# falownik_project.net
KiCad netlist of a schematic drawn in EAGLE
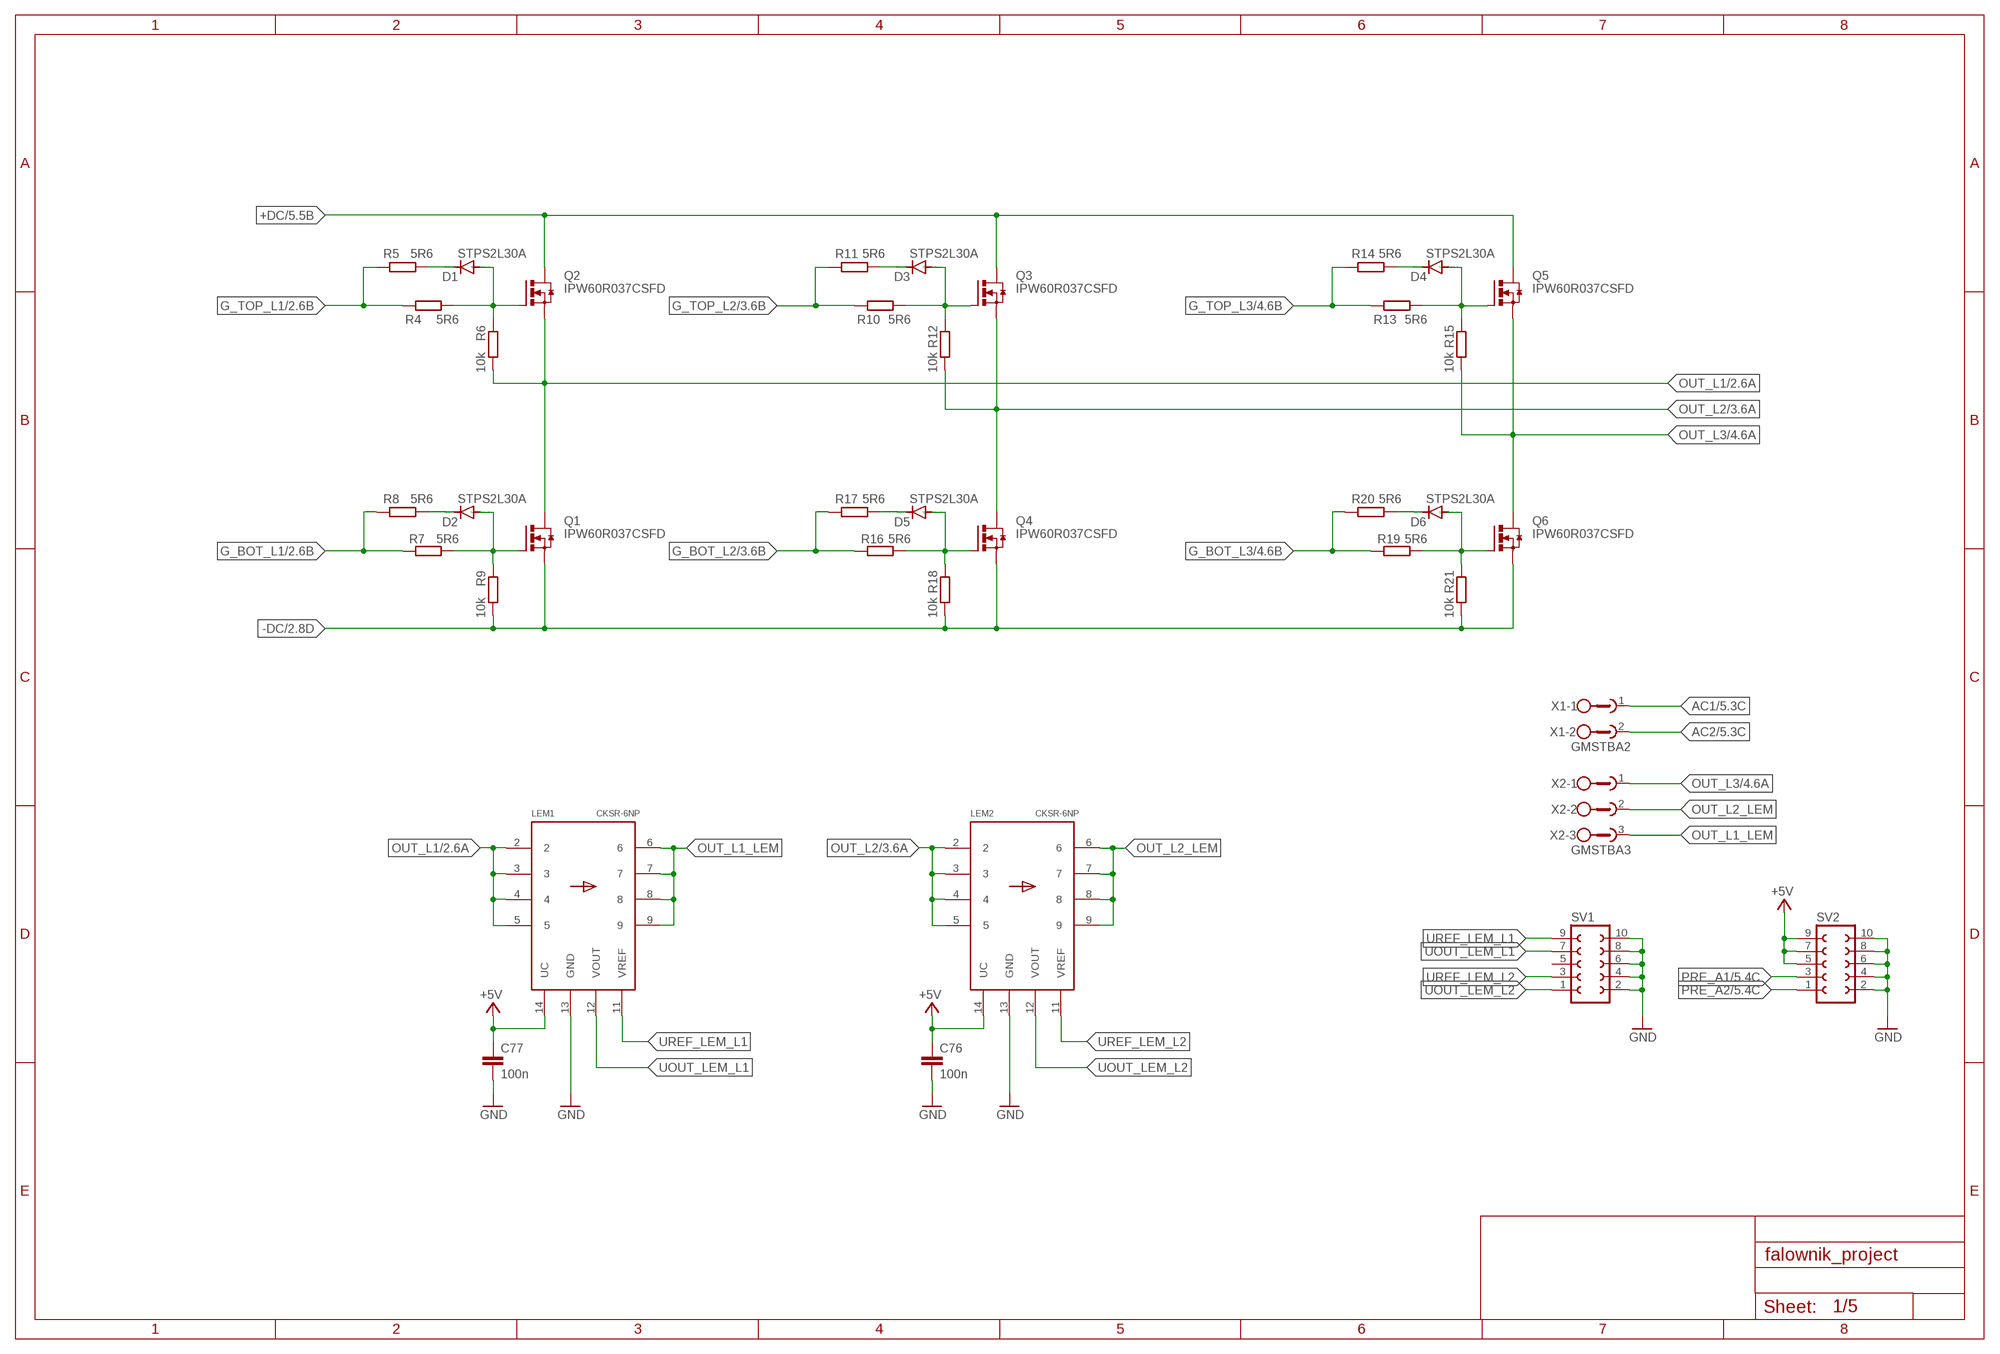
[diagram p0: schematic, sheet 1]
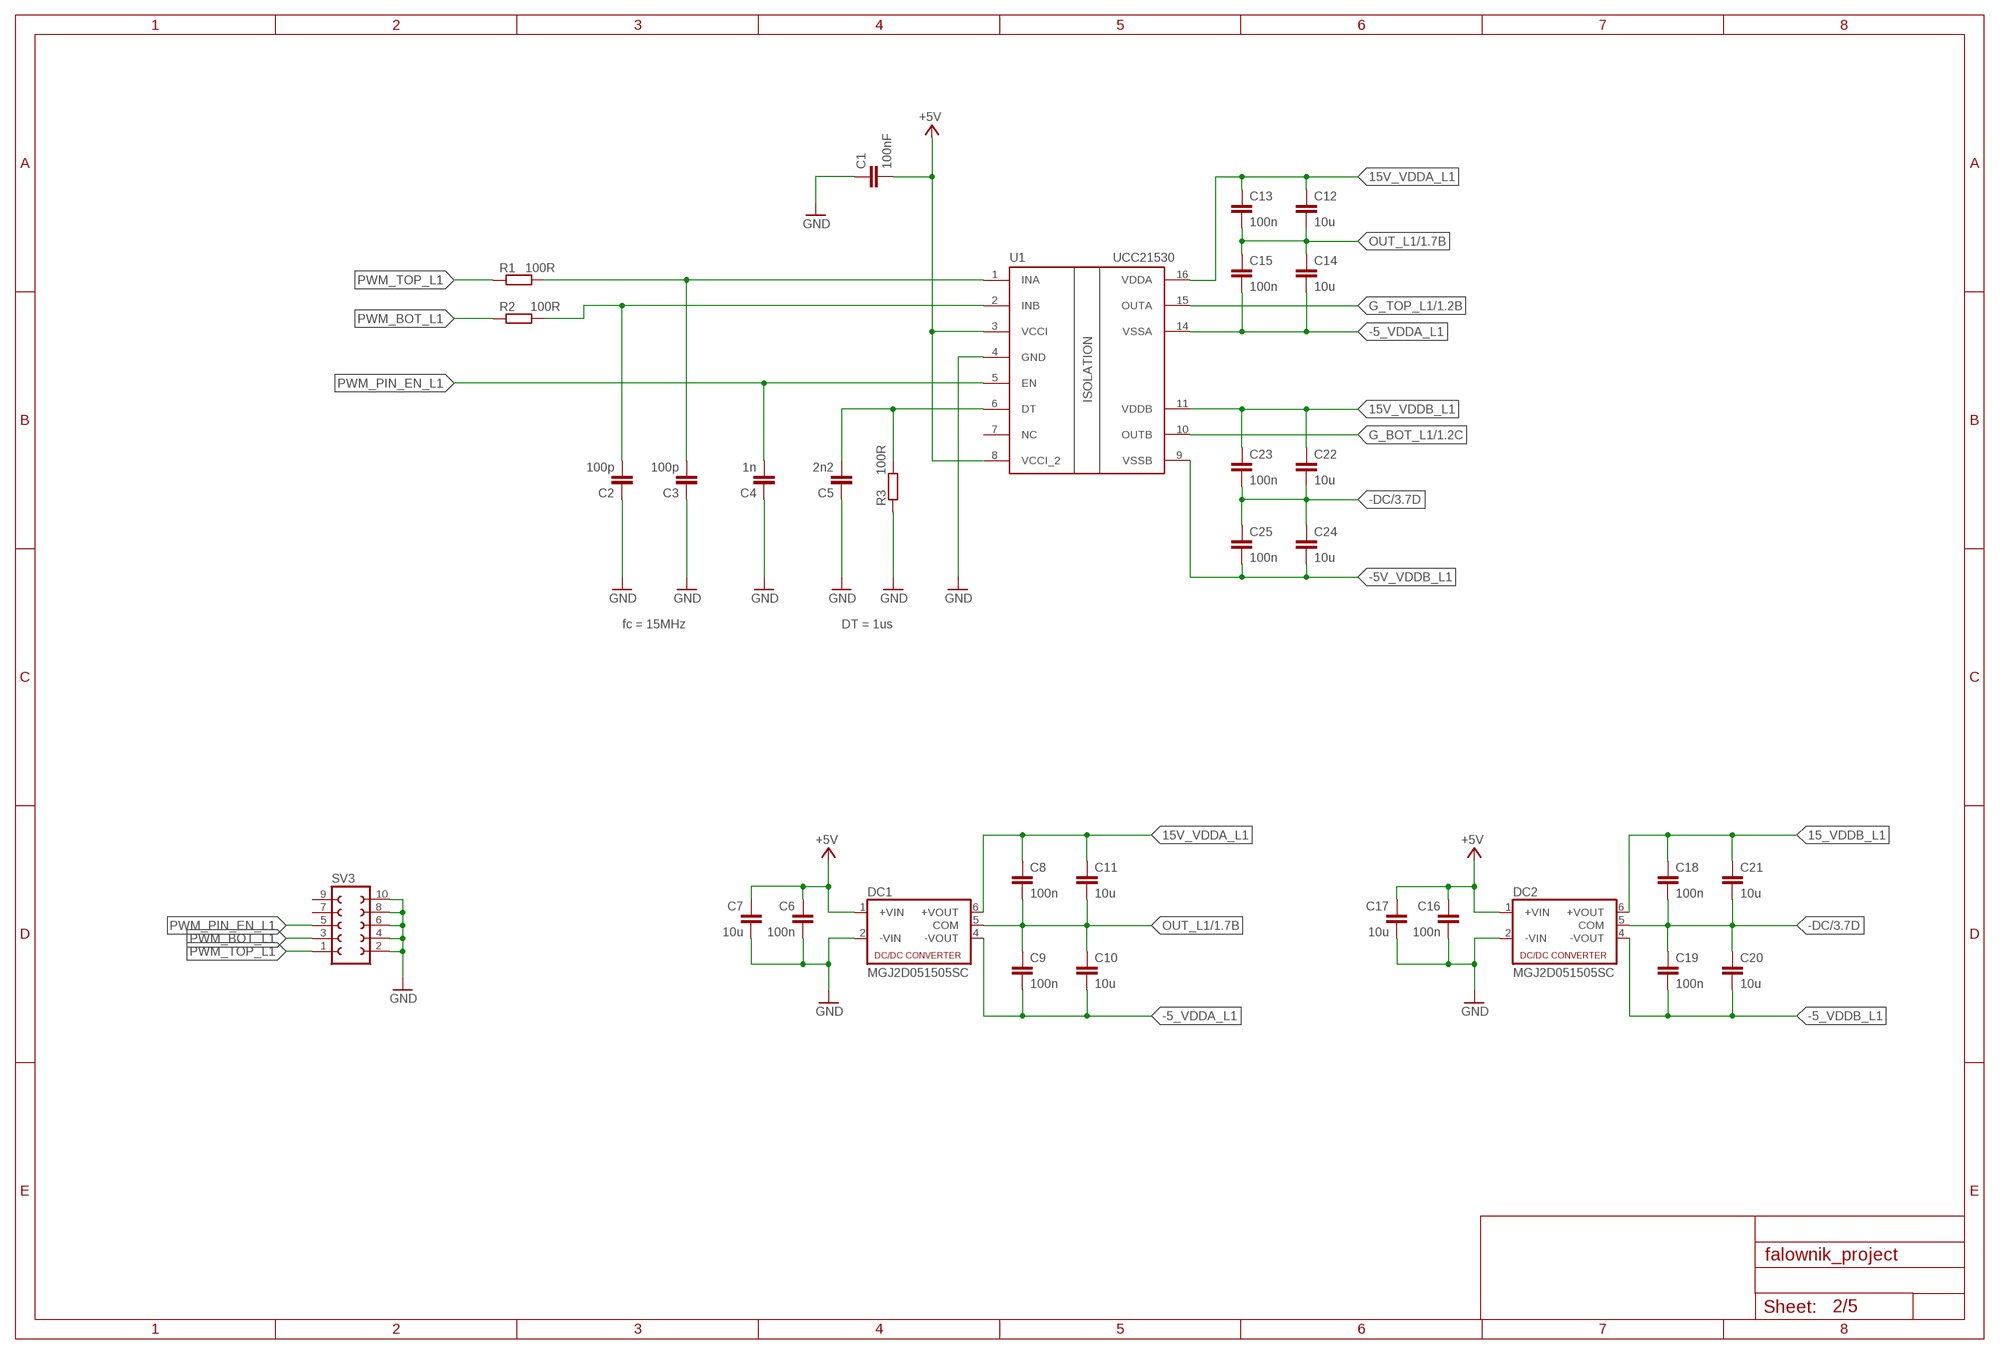
[diagram p1: schematic, sheet 2]
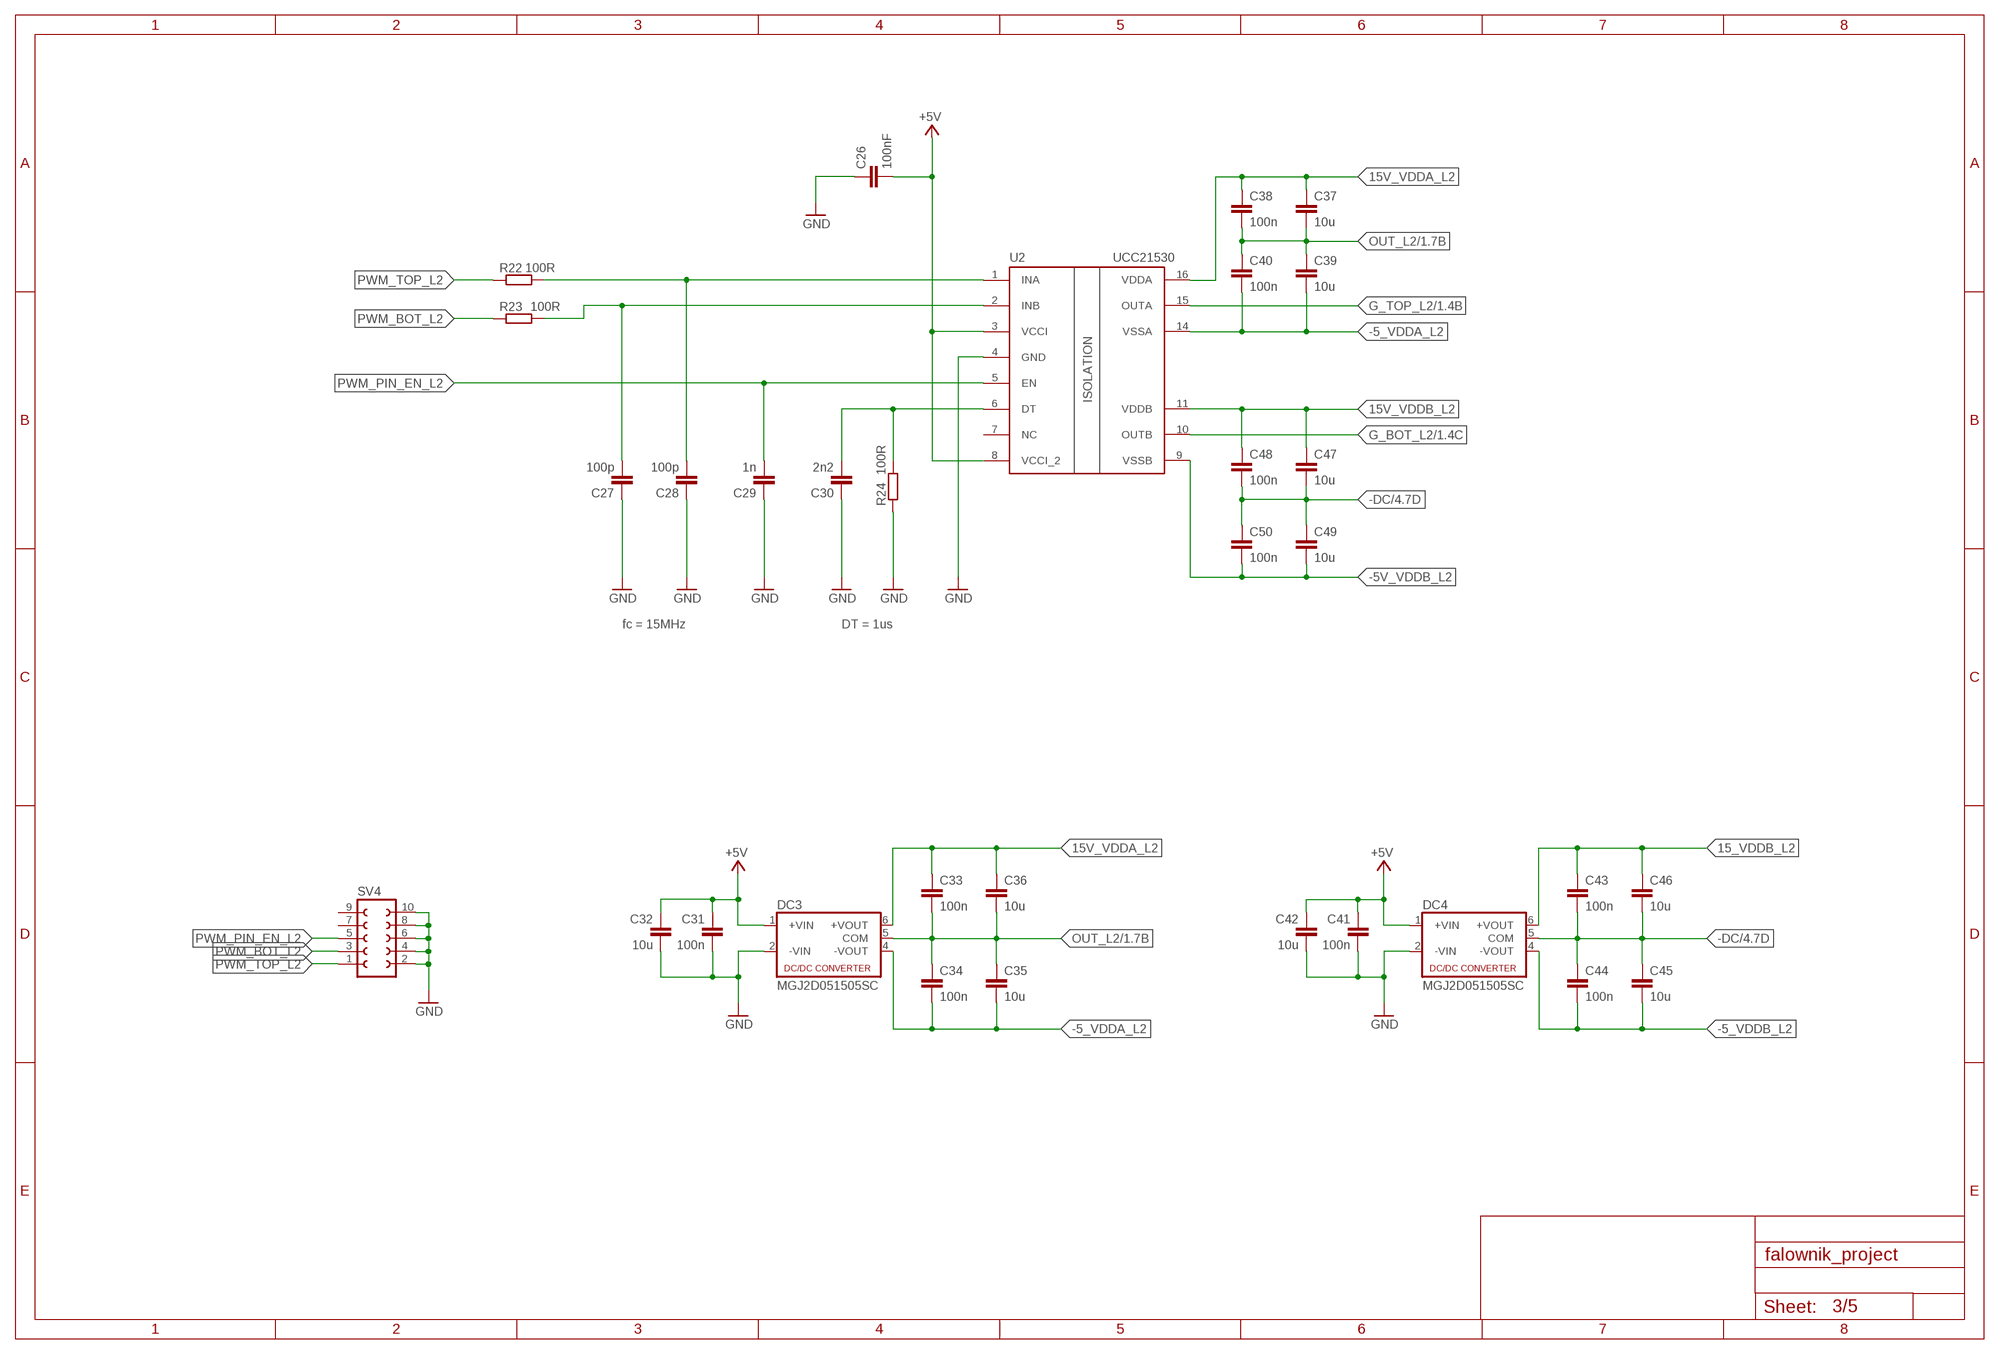
[diagram p2: schematic, sheet 3]
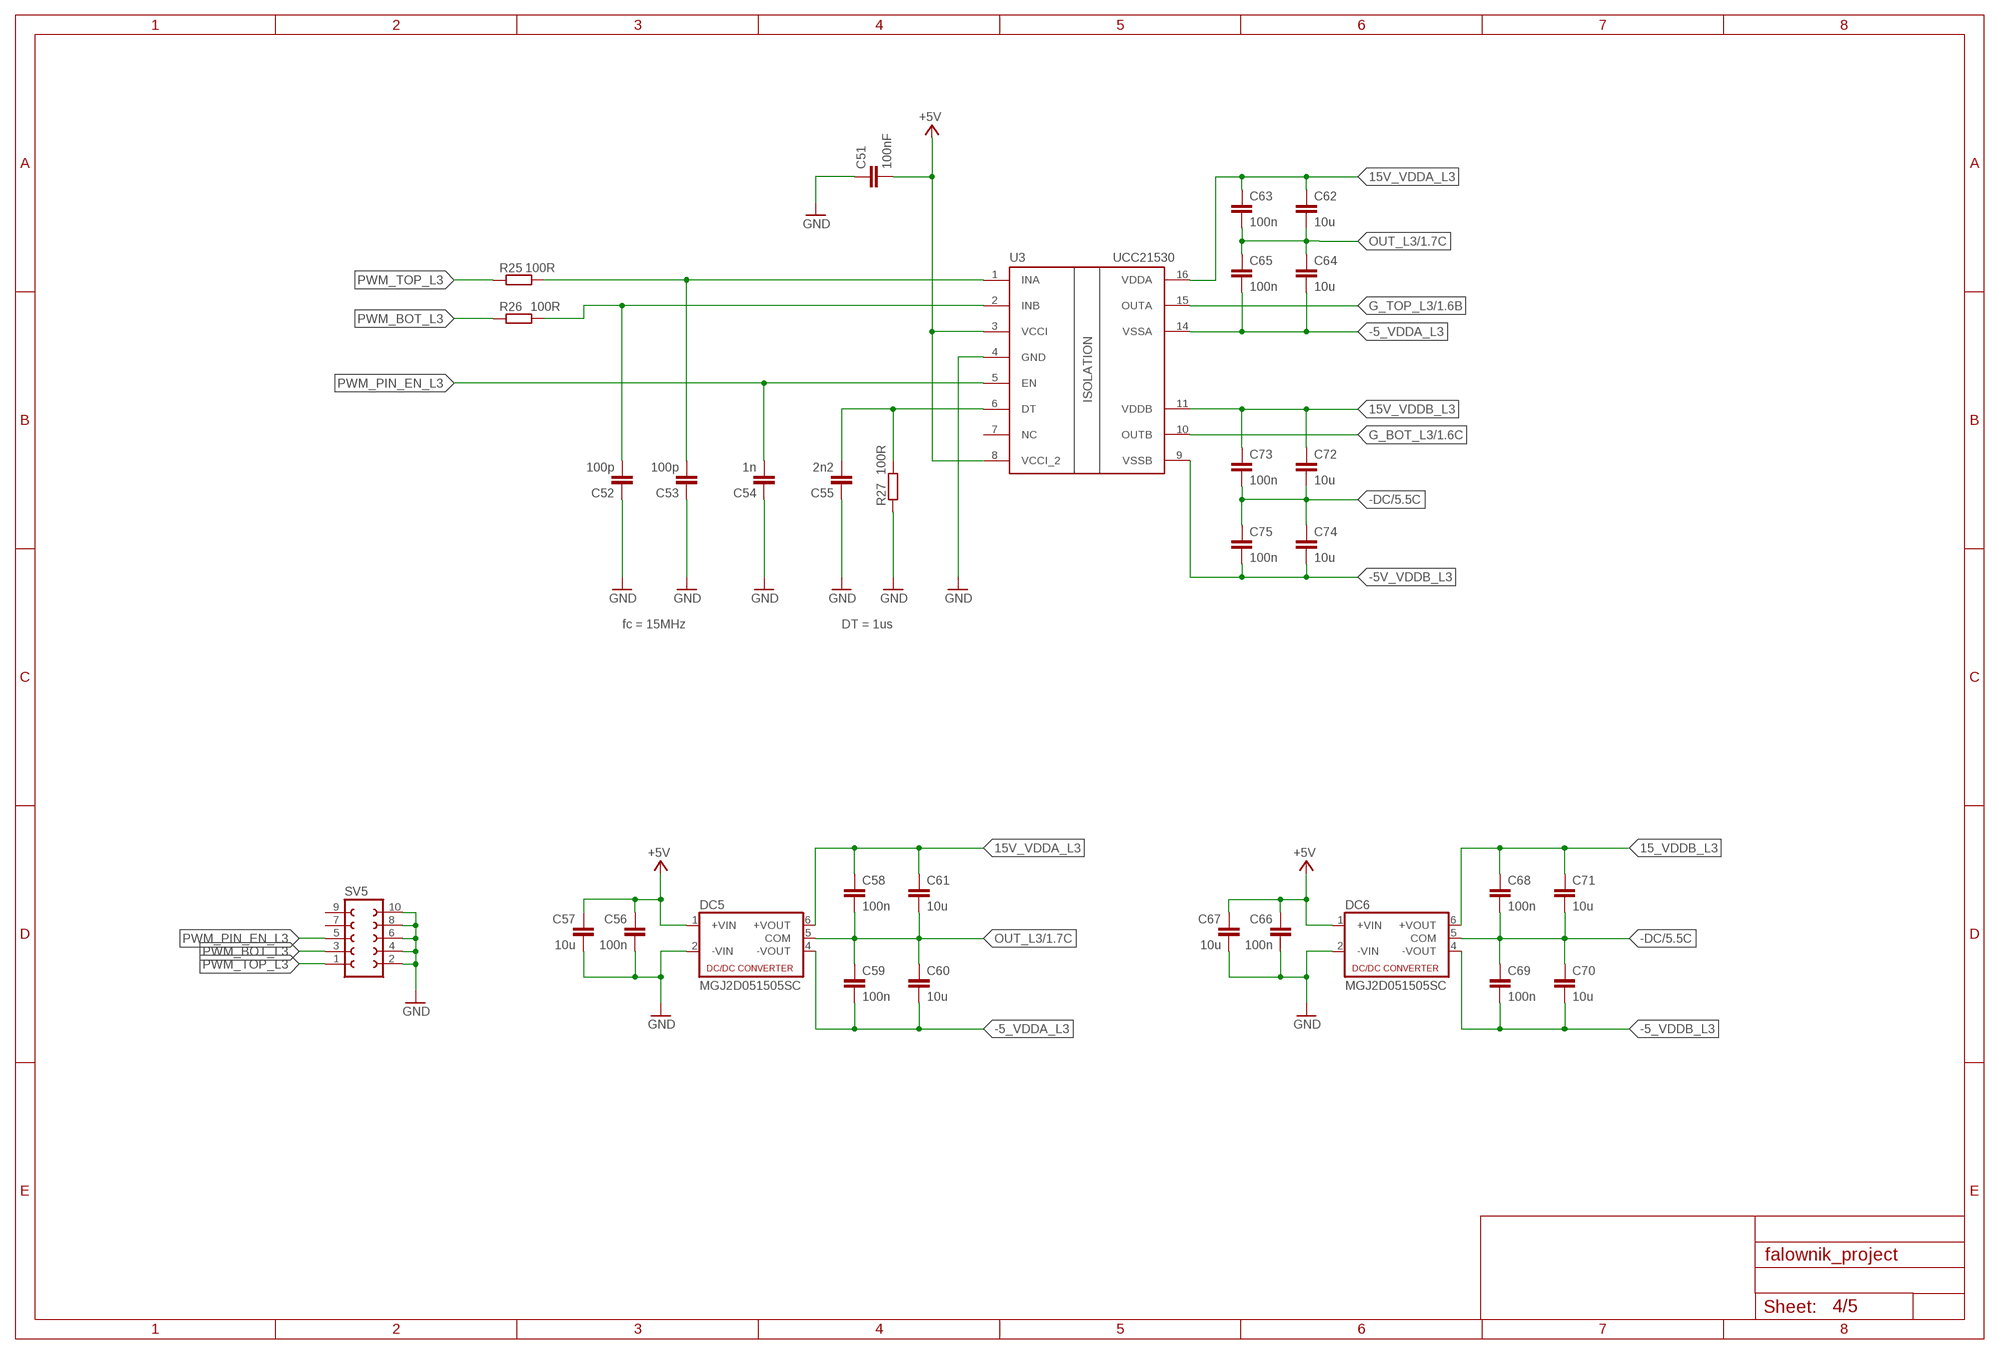
[diagram p3: schematic, sheet 4]
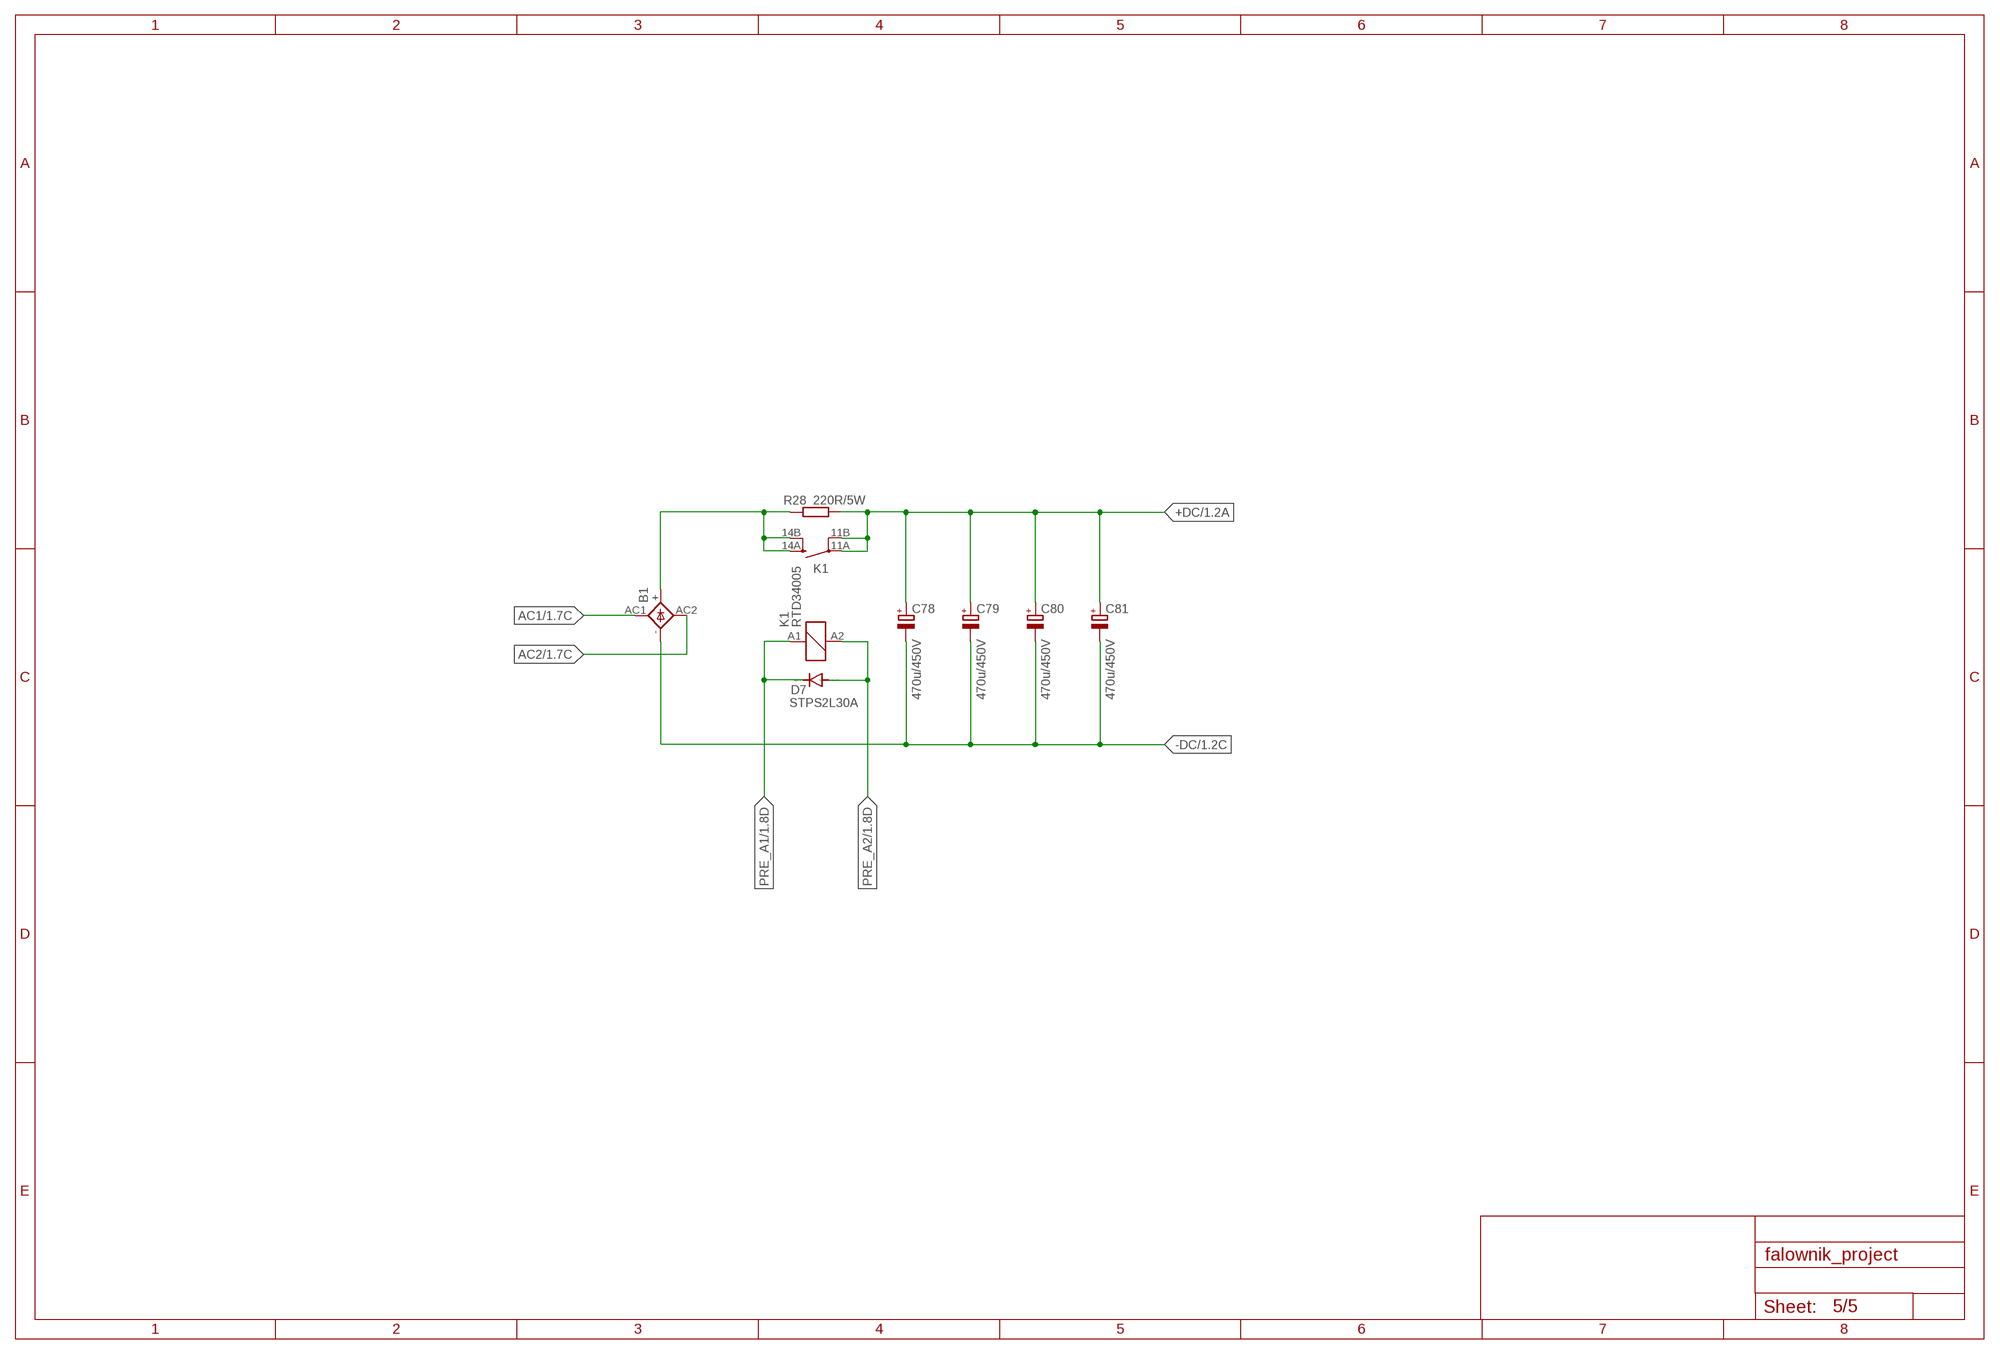
[diagram p4: schematic, sheet 5]

(export (version "E")
  (design (tool "Eeschema 10.0.6"))
  (components
    (comp (ref "C51")
      (value "100nF")
      (footprint "eagle-import:C0603")
      (libsource (lib "eagle-import") (part "C-EUC0603"))
    )
    (comp (ref "C52")
      (value "100p")
      (footprint "eagle-import:C0603")
      (libsource (lib "eagle-import") (part "C-EUC0603"))
    )
    (comp (ref "C53")
      (value "100p")
      (footprint "eagle-import:C0603")
      (libsource (lib "eagle-import") (part "C-EUC0603"))
    )
    (comp (ref "C54")
      (value "1n")
      (footprint "eagle-import:C0603")
      (libsource (lib "eagle-import") (part "C-EUC0603"))
    )
    (comp (ref "C55")
      (value "2n2")
      (footprint "eagle-import:C0603")
      (libsource (lib "eagle-import") (part "C-EUC0603"))
    )
    (comp (ref "C56")
      (value "100n")
      (footprint "eagle-import:C0603")
      (libsource (lib "eagle-import") (part "C-EUC0603"))
    )
    (comp (ref "C57")
      (value "10u")
      (footprint "eagle-import:C1206")
      (libsource (lib "eagle-import") (part "C-EUC1206"))
    )
    (comp (ref "C58")
      (value "100n")
      (footprint "eagle-import:C0603")
      (libsource (lib "eagle-import") (part "C-EUC0603"))
    )
    (comp (ref "C59")
      (value "100n")
      (footprint "eagle-import:C0603")
      (libsource (lib "eagle-import") (part "C-EUC0603"))
    )
    (comp (ref "C60")
      (value "10u")
      (footprint "eagle-import:C1206")
      (libsource (lib "eagle-import") (part "C-EUC1206"))
    )
    (comp (ref "C61")
      (value "10u")
      (footprint "eagle-import:C1210")
      (libsource (lib "eagle-import") (part "C-EUC1210"))
    )
    (comp (ref "C62")
      (value "10u")
      (footprint "eagle-import:C1210")
      (libsource (lib "eagle-import") (part "C-EUC1210"))
    )
    (comp (ref "C63")
      (value "100n")
      (footprint "eagle-import:C0603")
      (libsource (lib "eagle-import") (part "C-EUC0603"))
    )
    (comp (ref "C64")
      (value "10u")
      (footprint "eagle-import:C1206")
      (libsource (lib "eagle-import") (part "C-EUC1206"))
    )
    (comp (ref "C65")
      (value "100n")
      (footprint "eagle-import:C0603")
      (libsource (lib "eagle-import") (part "C-EUC0603"))
    )
    (comp (ref "C66")
      (value "100n")
      (footprint "eagle-import:C0603")
      (libsource (lib "eagle-import") (part "C-EUC0603"))
    )
    (comp (ref "C67")
      (value "10u")
      (footprint "eagle-import:C1206")
      (libsource (lib "eagle-import") (part "C-EUC1206"))
    )
    (comp (ref "C68")
      (value "100n")
      (footprint "eagle-import:C0603")
      (libsource (lib "eagle-import") (part "C-EUC0603"))
    )
    (comp (ref "C69")
      (value "100n")
      (footprint "eagle-import:C0603")
      (libsource (lib "eagle-import") (part "C-EUC0603"))
    )
    (comp (ref "C70")
      (value "10u")
      (footprint "eagle-import:C1206")
      (libsource (lib "eagle-import") (part "C-EUC1206"))
    )
    (comp (ref "C71")
      (value "10u")
      (footprint "eagle-import:C1210")
      (libsource (lib "eagle-import") (part "C-EUC1210"))
    )
    (comp (ref "C72")
      (value "10u")
      (footprint "eagle-import:C1210")
      (libsource (lib "eagle-import") (part "C-EUC1210"))
    )
    (comp (ref "C73")
      (value "100n")
      (footprint "eagle-import:C0603")
      (libsource (lib "eagle-import") (part "C-EUC0603"))
    )
    (comp (ref "C74")
      (value "10u")
      (footprint "eagle-import:C1206")
      (libsource (lib "eagle-import") (part "C-EUC1206"))
    )
    (comp (ref "C75")
      (value "100n")
      (footprint "eagle-import:C0603")
      (libsource (lib "eagle-import") (part "C-EUC0603"))
    )
    (comp (ref "DC5")
      (value "MGJ2D051505SC")
      (footprint "eagle-import:MGJ2D051505SC")
      (libsource (lib "eagle-import") (part "MGJ2D051505SC"))
    )
    (comp (ref "DC6")
      (value "MGJ2D051505SC")
      (footprint "eagle-import:MGJ2D051505SC")
      (libsource (lib "eagle-import") (part "MGJ2D051505SC"))
    )
    (comp (ref "R25")
      (value "100R")
      (footprint "eagle-import:R0603")
      (libsource (lib "eagle-import") (part "R-EU_R0603"))
    )
    (comp (ref "R26")
      (value "100R")
      (footprint "eagle-import:R0603")
      (libsource (lib "eagle-import") (part "R-EU_R0603"))
    )
    (comp (ref "R27")
      (value "100R")
      (footprint "eagle-import:R0603")
      (libsource (lib "eagle-import") (part "R-EU_R0603"))
    )
    (comp (ref "SV5")
      (value "FE05-2")
      (footprint "eagle-import:FE05-2")
      (libsource (lib "eagle-import") (part "FE05-2"))
    )
    (comp (ref "U3")
      (value "UCC21530")
      (footprint "eagle-import:SOIC-14")
      (libsource (lib "eagle-import") (part "UCC21530"))
    )
    (comp (ref "C26")
      (value "100nF")
      (footprint "eagle-import:C0603")
      (libsource (lib "eagle-import") (part "C-EUC0603"))
    )
    (comp (ref "C27")
      (value "100p")
      (footprint "eagle-import:C0603")
      (libsource (lib "eagle-import") (part "C-EUC0603"))
    )
    (comp (ref "C28")
      (value "100p")
      (footprint "eagle-import:C0603")
      (libsource (lib "eagle-import") (part "C-EUC0603"))
    )
    (comp (ref "C29")
      (value "1n")
      (footprint "eagle-import:C0603")
      (libsource (lib "eagle-import") (part "C-EUC0603"))
    )
    (comp (ref "C30")
      (value "2n2")
      (footprint "eagle-import:C0603")
      (libsource (lib "eagle-import") (part "C-EUC0603"))
    )
    (comp (ref "C31")
      (value "100n")
      (footprint "eagle-import:C0603")
      (libsource (lib "eagle-import") (part "C-EUC0603"))
    )
    (comp (ref "C32")
      (value "10u")
      (footprint "eagle-import:C1206")
      (libsource (lib "eagle-import") (part "C-EUC1206"))
    )
    (comp (ref "C33")
      (value "100n")
      (footprint "eagle-import:C0603")
      (libsource (lib "eagle-import") (part "C-EUC0603"))
    )
    (comp (ref "C34")
      (value "100n")
      (footprint "eagle-import:C0603")
      (libsource (lib "eagle-import") (part "C-EUC0603"))
    )
    (comp (ref "C35")
      (value "10u")
      (footprint "eagle-import:C1206")
      (libsource (lib "eagle-import") (part "C-EUC1206"))
    )
    (comp (ref "C36")
      (value "10u")
      (footprint "eagle-import:C1210")
      (libsource (lib "eagle-import") (part "C-EUC1210"))
    )
    (comp (ref "C37")
      (value "10u")
      (footprint "eagle-import:C1210")
      (libsource (lib "eagle-import") (part "C-EUC1210"))
    )
    (comp (ref "C38")
      (value "100n")
      (footprint "eagle-import:C0603")
      (libsource (lib "eagle-import") (part "C-EUC0603"))
    )
    (comp (ref "C39")
      (value "10u")
      (footprint "eagle-import:C1206")
      (libsource (lib "eagle-import") (part "C-EUC1206"))
    )
    (comp (ref "C40")
      (value "100n")
      (footprint "eagle-import:C0603")
      (libsource (lib "eagle-import") (part "C-EUC0603"))
    )
    (comp (ref "C41")
      (value "100n")
      (footprint "eagle-import:C0603")
      (libsource (lib "eagle-import") (part "C-EUC0603"))
    )
    (comp (ref "C42")
      (value "10u")
      (footprint "eagle-import:C1206")
      (libsource (lib "eagle-import") (part "C-EUC1206"))
    )
    (comp (ref "C43")
      (value "100n")
      (footprint "eagle-import:C0603")
      (libsource (lib "eagle-import") (part "C-EUC0603"))
    )
    (comp (ref "C44")
      (value "100n")
      (footprint "eagle-import:C0603")
      (libsource (lib "eagle-import") (part "C-EUC0603"))
    )
    (comp (ref "C45")
      (value "10u")
      (footprint "eagle-import:C1206")
      (libsource (lib "eagle-import") (part "C-EUC1206"))
    )
    (comp (ref "C46")
      (value "10u")
      (footprint "eagle-import:C1210")
      (libsource (lib "eagle-import") (part "C-EUC1210"))
    )
    (comp (ref "C47")
      (value "10u")
      (footprint "eagle-import:C1210")
      (libsource (lib "eagle-import") (part "C-EUC1210"))
    )
    (comp (ref "C48")
      (value "100n")
      (footprint "eagle-import:C0603")
      (libsource (lib "eagle-import") (part "C-EUC0603"))
    )
    (comp (ref "C49")
      (value "10u")
      (footprint "eagle-import:C1206")
      (libsource (lib "eagle-import") (part "C-EUC1206"))
    )
    (comp (ref "C50")
      (value "100n")
      (footprint "eagle-import:C0603")
      (libsource (lib "eagle-import") (part "C-EUC0603"))
    )
    (comp (ref "DC3")
      (value "MGJ2D051505SC")
      (footprint "eagle-import:MGJ2D051505SC")
      (libsource (lib "eagle-import") (part "MGJ2D051505SC"))
    )
    (comp (ref "DC4")
      (value "MGJ2D051505SC")
      (footprint "eagle-import:MGJ2D051505SC")
      (libsource (lib "eagle-import") (part "MGJ2D051505SC"))
    )
    (comp (ref "R22")
      (value "100R")
      (footprint "eagle-import:R0603")
      (libsource (lib "eagle-import") (part "R-EU_R0603"))
    )
    (comp (ref "R23")
      (value "100R")
      (footprint "eagle-import:R0603")
      (libsource (lib "eagle-import") (part "R-EU_R0603"))
    )
    (comp (ref "R24")
      (value "100R")
      (footprint "eagle-import:R0603")
      (libsource (lib "eagle-import") (part "R-EU_R0603"))
    )
    (comp (ref "SV4")
      (value "FE05-2")
      (footprint "eagle-import:FE05-2")
      (libsource (lib "eagle-import") (part "FE05-2"))
    )
    (comp (ref "U2")
      (value "UCC21530")
      (footprint "eagle-import:SOIC-14")
      (libsource (lib "eagle-import") (part "UCC21530"))
    )
    (comp (ref "C1")
      (value "100nF")
      (footprint "eagle-import:C0603")
      (libsource (lib "eagle-import") (part "C-EUC0603"))
    )
    (comp (ref "C2")
      (value "100p")
      (footprint "eagle-import:C0603")
      (libsource (lib "eagle-import") (part "C-EUC0603"))
    )
    (comp (ref "C3")
      (value "100p")
      (footprint "eagle-import:C0603")
      (libsource (lib "eagle-import") (part "C-EUC0603"))
    )
    (comp (ref "C4")
      (value "1n")
      (footprint "eagle-import:C0603")
      (libsource (lib "eagle-import") (part "C-EUC0603"))
    )
    (comp (ref "C5")
      (value "2n2")
      (footprint "eagle-import:C0603")
      (libsource (lib "eagle-import") (part "C-EUC0603"))
    )
    (comp (ref "C6")
      (value "100n")
      (footprint "eagle-import:C0603")
      (libsource (lib "eagle-import") (part "C-EUC0603"))
    )
    (comp (ref "C7")
      (value "10u")
      (footprint "eagle-import:C1206")
      (libsource (lib "eagle-import") (part "C-EUC1206"))
    )
    (comp (ref "C8")
      (value "100n")
      (footprint "eagle-import:C0603")
      (libsource (lib "eagle-import") (part "C-EUC0603"))
    )
    (comp (ref "C9")
      (value "100n")
      (footprint "eagle-import:C0603")
      (libsource (lib "eagle-import") (part "C-EUC0603"))
    )
    (comp (ref "C10")
      (value "10u")
      (footprint "eagle-import:C1206")
      (libsource (lib "eagle-import") (part "C-EUC1206"))
    )
    (comp (ref "C11")
      (value "10u")
      (footprint "eagle-import:C1210")
      (libsource (lib "eagle-import") (part "C-EUC1210"))
    )
    (comp (ref "C12")
      (value "10u")
      (footprint "eagle-import:C1210")
      (libsource (lib "eagle-import") (part "C-EUC1210"))
    )
    (comp (ref "C13")
      (value "100n")
      (footprint "eagle-import:C0603")
      (libsource (lib "eagle-import") (part "C-EUC0603"))
    )
    (comp (ref "C14")
      (value "10u")
      (footprint "eagle-import:C1206")
      (libsource (lib "eagle-import") (part "C-EUC1206"))
    )
    (comp (ref "C15")
      (value "100n")
      (footprint "eagle-import:C0603")
      (libsource (lib "eagle-import") (part "C-EUC0603"))
    )
    (comp (ref "C16")
      (value "100n")
      (footprint "eagle-import:C0603")
      (libsource (lib "eagle-import") (part "C-EUC0603"))
    )
    (comp (ref "C17")
      (value "10u")
      (footprint "eagle-import:C1206")
      (libsource (lib "eagle-import") (part "C-EUC1206"))
    )
    (comp (ref "C18")
      (value "100n")
      (footprint "eagle-import:C0603")
      (libsource (lib "eagle-import") (part "C-EUC0603"))
    )
    (comp (ref "C19")
      (value "100n")
      (footprint "eagle-import:C0603")
      (libsource (lib "eagle-import") (part "C-EUC0603"))
    )
    (comp (ref "C20")
      (value "10u")
      (footprint "eagle-import:C1206")
      (libsource (lib "eagle-import") (part "C-EUC1206"))
    )
    (comp (ref "C21")
      (value "10u")
      (footprint "eagle-import:C1210")
      (libsource (lib "eagle-import") (part "C-EUC1210"))
    )
    (comp (ref "C22")
      (value "10u")
      (footprint "eagle-import:C1210")
      (libsource (lib "eagle-import") (part "C-EUC1210"))
    )
    (comp (ref "C23")
      (value "100n")
      (footprint "eagle-import:C0603")
      (libsource (lib "eagle-import") (part "C-EUC0603"))
    )
    (comp (ref "C24")
      (value "10u")
      (footprint "eagle-import:C1206")
      (libsource (lib "eagle-import") (part "C-EUC1206"))
    )
    (comp (ref "C25")
      (value "100n")
      (footprint "eagle-import:C0603")
      (libsource (lib "eagle-import") (part "C-EUC0603"))
    )
    (comp (ref "DC1")
      (value "MGJ2D051505SC")
      (footprint "eagle-import:MGJ2D051505SC")
      (libsource (lib "eagle-import") (part "MGJ2D051505SC"))
    )
    (comp (ref "DC2")
      (value "MGJ2D051505SC")
      (footprint "eagle-import:MGJ2D051505SC")
      (libsource (lib "eagle-import") (part "MGJ2D051505SC"))
    )
    (comp (ref "R1")
      (value "100R")
      (footprint "eagle-import:R0603")
      (libsource (lib "eagle-import") (part "R-EU_R0603"))
    )
    (comp (ref "R2")
      (value "100R")
      (footprint "eagle-import:R0603")
      (libsource (lib "eagle-import") (part "R-EU_R0603"))
    )
    (comp (ref "R3")
      (value "100R")
      (footprint "eagle-import:R0603")
      (libsource (lib "eagle-import") (part "R-EU_R0603"))
    )
    (comp (ref "SV3")
      (value "FE05-2")
      (footprint "eagle-import:FE05-2")
      (libsource (lib "eagle-import") (part "FE05-2"))
    )
    (comp (ref "U1")
      (value "UCC21530")
      (footprint "eagle-import:SOIC-14")
      (libsource (lib "eagle-import") (part "UCC21530"))
    )
    (comp (ref "B1")
      (value "GBPC80X")
      (footprint "eagle-import:GBPC80X")
      (libsource (lib "eagle-import") (part "GBPC80X"))
    )
    (comp (ref "C78")
      (value "470u/450V")
      (footprint "eagle-import:EB30D")
      (libsource (lib "eagle-import") (part "CPOL-EUE10-30"))
    )
    (comp (ref "C79")
      (value "470u/450V")
      (footprint "eagle-import:EB30D")
      (libsource (lib "eagle-import") (part "CPOL-EUE10-30"))
    )
    (comp (ref "C80")
      (value "470u/450V")
      (footprint "eagle-import:EB30D")
      (libsource (lib "eagle-import") (part "CPOL-EUE10-30"))
    )
    (comp (ref "C81")
      (value "470u/450V")
      (footprint "eagle-import:EB30D")
      (libsource (lib "eagle-import") (part "CPOL-EUE10-30"))
    )
    (comp (ref "D7")
      (value "STPS2L30A")
      (footprint "eagle-import:DO214AC")
      (libsource (lib "eagle-import") (part "DIODE-DO214AC"))
    )
    (comp (ref "K1")
      (value "RTD34005")
      (footprint "eagle-import:RT-N_O16A5")
      (fields (field (name "MF") "TYCO ELECTRONICS"))
      (libsource (lib "eagle-import") (part "RTD34005"))
    )
    (comp (ref "R28")
      (value "220R/5W")
      (footprint "eagle-import:VTA52")
      (libsource (lib "eagle-import") (part "R-EU_VTA52"))
    )
    (comp (ref "C76")
      (value "100n")
      (footprint "eagle-import:C0805")
      (libsource (lib "eagle-import") (part "C-EUC0805"))
    )
    (comp (ref "C77")
      (value "100n")
      (footprint "eagle-import:C0805")
      (libsource (lib "eagle-import") (part "C-EUC0805"))
    )
    (comp (ref "D1")
      (value "STPS2L30A")
      (footprint "eagle-import:DO214AC")
      (libsource (lib "eagle-import") (part "DIODE-DO214AC"))
    )
    (comp (ref "D2")
      (value "STPS2L30A")
      (footprint "eagle-import:DO214AC")
      (libsource (lib "eagle-import") (part "DIODE-DO214AC"))
    )
    (comp (ref "D3")
      (value "STPS2L30A")
      (footprint "eagle-import:DO214AC")
      (libsource (lib "eagle-import") (part "DIODE-DO214AC"))
    )
    (comp (ref "D4")
      (value "STPS2L30A")
      (footprint "eagle-import:DO214AC")
      (libsource (lib "eagle-import") (part "DIODE-DO214AC"))
    )
    (comp (ref "D5")
      (value "STPS2L30A")
      (footprint "eagle-import:DO214AC")
      (libsource (lib "eagle-import") (part "DIODE-DO214AC"))
    )
    (comp (ref "D6")
      (value "STPS2L30A")
      (footprint "eagle-import:DO214AC")
      (libsource (lib "eagle-import") (part "DIODE-DO214AC"))
    )
    (comp (ref "LEM1")
      (value "CKSR-6NP")
      (footprint "eagle-import:CKSR")
      (libsource (lib "eagle-import") (part "CKSR-6NP"))
    )
    (comp (ref "LEM2")
      (value "CKSR-6NP")
      (footprint "eagle-import:CKSR")
      (libsource (lib "eagle-import") (part "CKSR-6NP"))
    )
    (comp (ref "Q1")
      (value "IPW60R037CSFD")
      (footprint "eagle-import:TO247BV")
      (libsource (lib "eagle-import") (part "IRFP240"))
    )
    (comp (ref "Q2")
      (value "IPW60R037CSFD")
      (footprint "eagle-import:TO247BV")
      (libsource (lib "eagle-import") (part "IRFP240"))
    )
    (comp (ref "Q3")
      (value "IPW60R037CSFD")
      (footprint "eagle-import:TO247BV")
      (libsource (lib "eagle-import") (part "IRFP240"))
    )
    (comp (ref "Q4")
      (value "IPW60R037CSFD")
      (footprint "eagle-import:TO247BV")
      (libsource (lib "eagle-import") (part "IRFP240"))
    )
    (comp (ref "Q5")
      (value "IPW60R037CSFD")
      (footprint "eagle-import:TO247BV")
      (libsource (lib "eagle-import") (part "IRFP240"))
    )
    (comp (ref "Q6")
      (value "IPW60R037CSFD")
      (footprint "eagle-import:TO247BV")
      (libsource (lib "eagle-import") (part "IRFP240"))
    )
    (comp (ref "R4")
      (value "5R6")
      (footprint "eagle-import:R0603")
      (libsource (lib "eagle-import") (part "R-EU_R0603"))
    )
    (comp (ref "R5")
      (value "5R6")
      (footprint "eagle-import:R0603")
      (libsource (lib "eagle-import") (part "R-EU_R0603"))
    )
    (comp (ref "R6")
      (value "10k")
      (footprint "eagle-import:R0603")
      (libsource (lib "eagle-import") (part "R-EU_R0603"))
    )
    (comp (ref "R7")
      (value "5R6")
      (footprint "eagle-import:R0603")
      (libsource (lib "eagle-import") (part "R-EU_R0603"))
    )
    (comp (ref "R8")
      (value "5R6")
      (footprint "eagle-import:R0603")
      (libsource (lib "eagle-import") (part "R-EU_R0603"))
    )
    (comp (ref "R9")
      (value "10k")
      (footprint "eagle-import:R0603")
      (libsource (lib "eagle-import") (part "R-EU_R0603"))
    )
    (comp (ref "R10")
      (value "5R6")
      (footprint "eagle-import:R0603")
      (libsource (lib "eagle-import") (part "R-EU_R0603"))
    )
    (comp (ref "R11")
      (value "5R6")
      (footprint "eagle-import:R0603")
      (libsource (lib "eagle-import") (part "R-EU_R0603"))
    )
    (comp (ref "R12")
      (value "10k")
      (footprint "eagle-import:R0603")
      (libsource (lib "eagle-import") (part "R-EU_R0603"))
    )
    (comp (ref "R13")
      (value "5R6")
      (footprint "eagle-import:R0603")
      (libsource (lib "eagle-import") (part "R-EU_R0603"))
    )
    (comp (ref "R14")
      (value "5R6")
      (footprint "eagle-import:R0603")
      (libsource (lib "eagle-import") (part "R-EU_R0603"))
    )
    (comp (ref "R15")
      (value "10k")
      (footprint "eagle-import:R0603")
      (libsource (lib "eagle-import") (part "R-EU_R0603"))
    )
    (comp (ref "R16")
      (value "5R6")
      (footprint "eagle-import:R0603")
      (libsource (lib "eagle-import") (part "R-EU_R0603"))
    )
    (comp (ref "R17")
      (value "5R6")
      (footprint "eagle-import:R0603")
      (libsource (lib "eagle-import") (part "R-EU_R0603"))
    )
    (comp (ref "R18")
      (value "10k")
      (footprint "eagle-import:R0603")
      (libsource (lib "eagle-import") (part "R-EU_R0603"))
    )
    (comp (ref "R19")
      (value "5R6")
      (footprint "eagle-import:R0603")
      (libsource (lib "eagle-import") (part "R-EU_R0603"))
    )
    (comp (ref "R20")
      (value "5R6")
      (footprint "eagle-import:R0603")
      (libsource (lib "eagle-import") (part "R-EU_R0603"))
    )
    (comp (ref "R21")
      (value "10k")
      (footprint "eagle-import:R0603")
      (libsource (lib "eagle-import") (part "R-EU_R0603"))
    )
    (comp (ref "SV1")
      (value "FE05-2")
      (footprint "eagle-import:FE05-2")
      (libsource (lib "eagle-import") (part "FE05-2"))
    )
    (comp (ref "SV2")
      (value "FE05-2")
      (footprint "eagle-import:FE05-2")
      (libsource (lib "eagle-import") (part "FE05-2"))
    )
    (comp (ref "X1")
      (value "GMSTBA2")
      (footprint "eagle-import:GMSTBA2")
      (fields (field (name "MF") "FARNELL") (field (name "MPN") "1757242"))
      (libsource (lib "eagle-import") (part "GMSTBA2"))
    )
    (comp (ref "X2")
      (value "GMSTBA3")
      (footprint "eagle-import:GMSTBA3")
      (fields (field (name "MF") "FARNELL") (field (name "MPN") "1757255"))
      (libsource (lib "eagle-import") (part "GMSTBA3"))
    )
  )
  (nets
    (net (code "1") (name "+5V") (class "Default")
      (node (ref "C1") (pin "2") (pinfunction "2_2") (pintype "passive"))
      (node (ref "C16") (pin "1") (pinfunction "1_1") (pintype "passive"))
      (node (ref "C17") (pin "1") (pinfunction "1_1") (pintype "passive"))
      (node (ref "C26") (pin "2") (pinfunction "2_2") (pintype "passive"))
      (node (ref "C31") (pin "1") (pinfunction "1_1") (pintype "passive"))
      (node (ref "C32") (pin "1") (pinfunction "1_1") (pintype "passive"))
      (node (ref "C41") (pin "1") (pinfunction "1_1") (pintype "passive"))
      (node (ref "C42") (pin "1") (pinfunction "1_1") (pintype "passive"))
      (node (ref "C51") (pin "2") (pinfunction "2_2") (pintype "passive"))
      (node (ref "C56") (pin "1") (pinfunction "1_1") (pintype "passive"))
      (node (ref "C57") (pin "1") (pinfunction "1_1") (pintype "passive"))
      (node (ref "C6") (pin "1") (pinfunction "1_1") (pintype "passive"))
      (node (ref "C66") (pin "1") (pinfunction "1_1") (pintype "passive"))
      (node (ref "C67") (pin "1") (pinfunction "1_1") (pintype "passive"))
      (node (ref "C7") (pin "1") (pinfunction "1_1") (pintype "passive"))
      (node (ref "C76") (pin "1") (pinfunction "1_1") (pintype "passive"))
      (node (ref "C77") (pin "1") (pinfunction "1_1") (pintype "passive"))
      (node (ref "DC1") (pin "1") (pinfunction "+VIN_1") (pintype "passive"))
      (node (ref "DC2") (pin "1") (pinfunction "+VIN_1") (pintype "passive"))
      (node (ref "DC3") (pin "1") (pinfunction "+VIN_1") (pintype "passive"))
      (node (ref "DC4") (pin "1") (pinfunction "+VIN_1") (pintype "passive"))
      (node (ref "DC5") (pin "1") (pinfunction "+VIN_1") (pintype "passive"))
      (node (ref "DC6") (pin "1") (pinfunction "+VIN_1") (pintype "passive"))
      (node (ref "LEM1") (pin "14") (pinfunction "UC_14") (pintype "bidirectional"))
      (node (ref "LEM2") (pin "14") (pinfunction "UC_14") (pintype "bidirectional"))
      (node (ref "SV2") (pin "5") (pinfunction "5_5") (pintype "passive"))
      (node (ref "SV2") (pin "7") (pinfunction "7_7") (pintype "passive"))
      (node (ref "SV2") (pin "9") (pinfunction "9_9") (pintype "passive"))
      (node (ref "U1") (pin "3") (pinfunction "VCCI_3") (pintype "bidirectional"))
      (node (ref "U1") (pin "8") (pinfunction "VCCI_2_8") (pintype "bidirectional"))
      (node (ref "U2") (pin "3") (pinfunction "VCCI_3") (pintype "bidirectional"))
      (node (ref "U2") (pin "8") (pinfunction "VCCI_2_8") (pintype "bidirectional"))
      (node (ref "U3") (pin "3") (pinfunction "VCCI_3") (pintype "bidirectional"))
      (node (ref "U3") (pin "8") (pinfunction "VCCI_2_8") (pintype "bidirectional"))
    )
    (net (code "2") (name "+DC") (class "Default")
      (node (ref "C78") (pin "+") (pinfunction "+_+") (pintype "passive"))
      (node (ref "C79") (pin "+") (pinfunction "+_+") (pintype "passive"))
      (node (ref "C80") (pin "+") (pinfunction "+_+") (pintype "passive"))
      (node (ref "C81") (pin "+") (pinfunction "+_+") (pintype "passive"))
      (node (ref "K1") (pin "11A") (pinfunction "PA_11A") (pintype "passive"))
      (node (ref "K1") (pin "11B") (pinfunction "PB_11B") (pintype "passive"))
      (node (ref "Q2") (pin "D") (pinfunction "D_D") (pintype "passive"))
      (node (ref "Q3") (pin "D") (pinfunction "D_D") (pintype "passive"))
      (node (ref "Q5") (pin "D") (pinfunction "D_D") (pintype "passive"))
      (node (ref "R28") (pin "2") (pinfunction "2_2") (pintype "passive"))
    )
    (net (code "3") (name "-5V_VDDB_L1") (class "Default")
      (node (ref "C24") (pin "2") (pinfunction "2_2") (pintype "passive"))
      (node (ref "C25") (pin "2") (pinfunction "2_2") (pintype "passive"))
      (node (ref "U1") (pin "9") (pinfunction "VSSB_9") (pintype "bidirectional"))
    )
    (net (code "4") (name "-5V_VDDB_L2") (class "Default")
      (node (ref "C49") (pin "2") (pinfunction "2_2") (pintype "passive"))
      (node (ref "C50") (pin "2") (pinfunction "2_2") (pintype "passive"))
      (node (ref "U2") (pin "9") (pinfunction "VSSB_9") (pintype "bidirectional"))
    )
    (net (code "5") (name "-5V_VDDB_L3") (class "Default")
      (node (ref "C74") (pin "2") (pinfunction "2_2") (pintype "passive"))
      (node (ref "C75") (pin "2") (pinfunction "2_2") (pintype "passive"))
      (node (ref "U3") (pin "9") (pinfunction "VSSB_9") (pintype "bidirectional"))
    )
    (net (code "6") (name "-5_VDDA_L1") (class "Default")
      (node (ref "C10") (pin "2") (pinfunction "2_2") (pintype "passive"))
      (node (ref "C9") (pin "2") (pinfunction "2_2") (pintype "passive"))
      (node (ref "DC1") (pin "4") (pinfunction "-VOUT_4") (pintype "passive"))
    )
    (net (code "7") (name "-5_VDDA_L2") (class "Default")
      (node (ref "C34") (pin "2") (pinfunction "2_2") (pintype "passive"))
      (node (ref "C35") (pin "2") (pinfunction "2_2") (pintype "passive"))
      (node (ref "DC3") (pin "4") (pinfunction "-VOUT_4") (pintype "passive"))
    )
    (net (code "8") (name "-5_VDDA_L3") (class "Default")
      (node (ref "C59") (pin "2") (pinfunction "2_2") (pintype "passive"))
      (node (ref "C60") (pin "2") (pinfunction "2_2") (pintype "passive"))
      (node (ref "DC5") (pin "4") (pinfunction "-VOUT_4") (pintype "passive"))
    )
    (net (code "9") (name "-5_VDDB_L1") (class "Default")
      (node (ref "C19") (pin "2") (pinfunction "2_2") (pintype "passive"))
      (node (ref "C20") (pin "2") (pinfunction "2_2") (pintype "passive"))
      (node (ref "DC2") (pin "4") (pinfunction "-VOUT_4") (pintype "passive"))
    )
    (net (code "10") (name "-5_VDDB_L2") (class "Default")
      (node (ref "C44") (pin "2") (pinfunction "2_2") (pintype "passive"))
      (node (ref "C45") (pin "2") (pinfunction "2_2") (pintype "passive"))
      (node (ref "DC4") (pin "4") (pinfunction "-VOUT_4") (pintype "passive"))
    )
    (net (code "11") (name "-5_VDDB_L3") (class "Default")
      (node (ref "C69") (pin "2") (pinfunction "2_2") (pintype "passive"))
      (node (ref "C70") (pin "2") (pinfunction "2_2") (pintype "passive"))
      (node (ref "DC6") (pin "4") (pinfunction "-VOUT_4") (pintype "passive"))
    )
    (net (code "12") (name "-DC") (class "Default")
      (node (ref "B1") (pin "-") (pinfunction "-_-") (pintype "passive"))
      (node (ref "C18") (pin "2") (pinfunction "2_2") (pintype "passive"))
      (node (ref "C19") (pin "1") (pinfunction "1_1") (pintype "passive"))
      (node (ref "C20") (pin "1") (pinfunction "1_1") (pintype "passive"))
      (node (ref "C21") (pin "2") (pinfunction "2_2") (pintype "passive"))
      (node (ref "C22") (pin "2") (pinfunction "2_2") (pintype "passive"))
      (node (ref "C23") (pin "2") (pinfunction "2_2") (pintype "passive"))
      (node (ref "C24") (pin "1") (pinfunction "1_1") (pintype "passive"))
      (node (ref "C25") (pin "1") (pinfunction "1_1") (pintype "passive"))
      (node (ref "C43") (pin "2") (pinfunction "2_2") (pintype "passive"))
      (node (ref "C44") (pin "1") (pinfunction "1_1") (pintype "passive"))
      (node (ref "C45") (pin "1") (pinfunction "1_1") (pintype "passive"))
      (node (ref "C46") (pin "2") (pinfunction "2_2") (pintype "passive"))
      (node (ref "C47") (pin "2") (pinfunction "2_2") (pintype "passive"))
      (node (ref "C48") (pin "2") (pinfunction "2_2") (pintype "passive"))
      (node (ref "C49") (pin "1") (pinfunction "1_1") (pintype "passive"))
      (node (ref "C50") (pin "1") (pinfunction "1_1") (pintype "passive"))
      (node (ref "C68") (pin "2") (pinfunction "2_2") (pintype "passive"))
      (node (ref "C69") (pin "1") (pinfunction "1_1") (pintype "passive"))
      (node (ref "C70") (pin "1") (pinfunction "1_1") (pintype "passive"))
      (node (ref "C71") (pin "2") (pinfunction "2_2") (pintype "passive"))
      (node (ref "C72") (pin "2") (pinfunction "2_2") (pintype "passive"))
      (node (ref "C73") (pin "2") (pinfunction "2_2") (pintype "passive"))
      (node (ref "C74") (pin "1") (pinfunction "1_1") (pintype "passive"))
      (node (ref "C75") (pin "1") (pinfunction "1_1") (pintype "passive"))
      (node (ref "C78") (pin "-") (pinfunction "-_-") (pintype "passive"))
      (node (ref "C79") (pin "-") (pinfunction "-_-") (pintype "passive"))
      (node (ref "C80") (pin "-") (pinfunction "-_-") (pintype "passive"))
      (node (ref "C81") (pin "-") (pinfunction "-_-") (pintype "passive"))
      (node (ref "DC2") (pin "5") (pinfunction "COM_5") (pintype "passive"))
      (node (ref "DC4") (pin "5") (pinfunction "COM_5") (pintype "passive"))
      (node (ref "DC6") (pin "5") (pinfunction "COM_5") (pintype "passive"))
      (node (ref "Q1") (pin "S") (pinfunction "S_S") (pintype "passive"))
      (node (ref "Q4") (pin "S") (pinfunction "S_S") (pintype "passive"))
      (node (ref "Q6") (pin "S") (pinfunction "S_S") (pintype "passive"))
      (node (ref "R18") (pin "2") (pinfunction "2_2") (pintype "passive"))
      (node (ref "R21") (pin "2") (pinfunction "2_2") (pintype "passive"))
      (node (ref "R9") (pin "2") (pinfunction "2_2") (pintype "passive"))
    )
    (net (code "13") (name "15V_VDDA_L1") (class "Default")
      (node (ref "C11") (pin "1") (pinfunction "1_1") (pintype "passive"))
      (node (ref "C8") (pin "1") (pinfunction "1_1") (pintype "passive"))
      (node (ref "DC1") (pin "6") (pinfunction "+VOUT_6") (pintype "passive"))
    )
    (net (code "14") (name "15V_VDDA_L2") (class "Default")
      (node (ref "C33") (pin "1") (pinfunction "1_1") (pintype "passive"))
      (node (ref "C36") (pin "1") (pinfunction "1_1") (pintype "passive"))
      (node (ref "DC3") (pin "6") (pinfunction "+VOUT_6") (pintype "passive"))
    )
    (net (code "15") (name "15V_VDDA_L3") (class "Default")
      (node (ref "C58") (pin "1") (pinfunction "1_1") (pintype "passive"))
      (node (ref "C61") (pin "1") (pinfunction "1_1") (pintype "passive"))
      (node (ref "DC5") (pin "6") (pinfunction "+VOUT_6") (pintype "passive"))
    )
    (net (code "16") (name "15V_VDDB_L1") (class "Default")
      (node (ref "C22") (pin "1") (pinfunction "1_1") (pintype "passive"))
      (node (ref "C23") (pin "1") (pinfunction "1_1") (pintype "passive"))
      (node (ref "U1") (pin "11") (pinfunction "VDDB_11") (pintype "bidirectional"))
    )
    (net (code "17") (name "15V_VDDB_L2") (class "Default")
      (node (ref "C47") (pin "1") (pinfunction "1_1") (pintype "passive"))
      (node (ref "C48") (pin "1") (pinfunction "1_1") (pintype "passive"))
      (node (ref "U2") (pin "11") (pinfunction "VDDB_11") (pintype "bidirectional"))
    )
    (net (code "18") (name "15V_VDDB_L3") (class "Default")
      (node (ref "C72") (pin "1") (pinfunction "1_1") (pintype "passive"))
      (node (ref "C73") (pin "1") (pinfunction "1_1") (pintype "passive"))
      (node (ref "U3") (pin "11") (pinfunction "VDDB_11") (pintype "bidirectional"))
    )
    (net (code "19") (name "15_VDDB_L1") (class "Default")
      (node (ref "C18") (pin "1") (pinfunction "1_1") (pintype "passive"))
      (node (ref "C21") (pin "1") (pinfunction "1_1") (pintype "passive"))
      (node (ref "DC2") (pin "6") (pinfunction "+VOUT_6") (pintype "passive"))
    )
    (net (code "20") (name "15_VDDB_L2") (class "Default")
      (node (ref "C43") (pin "1") (pinfunction "1_1") (pintype "passive"))
      (node (ref "C46") (pin "1") (pinfunction "1_1") (pintype "passive"))
      (node (ref "DC4") (pin "6") (pinfunction "+VOUT_6") (pintype "passive"))
    )
    (net (code "21") (name "15_VDDB_L3") (class "Default")
      (node (ref "C68") (pin "1") (pinfunction "1_1") (pintype "passive"))
      (node (ref "C71") (pin "1") (pinfunction "1_1") (pintype "passive"))
      (node (ref "DC6") (pin "6") (pinfunction "+VOUT_6") (pintype "passive"))
    )
    (net (code "22") (name "AC1") (class "Default")
      (node (ref "B1") (pin "AC1") (pinfunction "AC1_AC1") (pintype "passive"))
      (node (ref "X1") (pin "1") (pinfunction "1_1") (pintype "passive"))
    )
    (net (code "23") (name "AC2") (class "Default")
      (node (ref "B1") (pin "AC2") (pinfunction "AC2_AC2") (pintype "passive"))
      (node (ref "X1") (pin "2") (pinfunction "1_2") (pintype "passive"))
    )
    (net (code "24") (name "GND") (class "Default")
      (node (ref "C1") (pin "1") (pinfunction "1_1") (pintype "passive"))
      (node (ref "C16") (pin "2") (pinfunction "2_2") (pintype "passive"))
      (node (ref "C17") (pin "2") (pinfunction "2_2") (pintype "passive"))
      (node (ref "C2") (pin "1") (pinfunction "1_1") (pintype "passive"))
      (node (ref "C26") (pin "1") (pinfunction "1_1") (pintype "passive"))
      (node (ref "C27") (pin "1") (pinfunction "1_1") (pintype "passive"))
      (node (ref "C28") (pin "1") (pinfunction "1_1") (pintype "passive"))
      (node (ref "C29") (pin "1") (pinfunction "1_1") (pintype "passive"))
      (node (ref "C3") (pin "1") (pinfunction "1_1") (pintype "passive"))
      (node (ref "C30") (pin "1") (pinfunction "1_1") (pintype "passive"))
      (node (ref "C31") (pin "2") (pinfunction "2_2") (pintype "passive"))
      (node (ref "C32") (pin "2") (pinfunction "2_2") (pintype "passive"))
      (node (ref "C4") (pin "1") (pinfunction "1_1") (pintype "passive"))
      (node (ref "C41") (pin "2") (pinfunction "2_2") (pintype "passive"))
      (node (ref "C42") (pin "2") (pinfunction "2_2") (pintype "passive"))
      (node (ref "C5") (pin "1") (pinfunction "1_1") (pintype "passive"))
      (node (ref "C51") (pin "1") (pinfunction "1_1") (pintype "passive"))
      (node (ref "C52") (pin "1") (pinfunction "1_1") (pintype "passive"))
      (node (ref "C53") (pin "1") (pinfunction "1_1") (pintype "passive"))
      (node (ref "C54") (pin "1") (pinfunction "1_1") (pintype "passive"))
      (node (ref "C55") (pin "1") (pinfunction "1_1") (pintype "passive"))
      (node (ref "C56") (pin "2") (pinfunction "2_2") (pintype "passive"))
      (node (ref "C57") (pin "2") (pinfunction "2_2") (pintype "passive"))
      (node (ref "C6") (pin "2") (pinfunction "2_2") (pintype "passive"))
      (node (ref "C66") (pin "2") (pinfunction "2_2") (pintype "passive"))
      (node (ref "C67") (pin "2") (pinfunction "2_2") (pintype "passive"))
      (node (ref "C7") (pin "2") (pinfunction "2_2") (pintype "passive"))
      (node (ref "C76") (pin "2") (pinfunction "2_2") (pintype "passive"))
      (node (ref "C77") (pin "2") (pinfunction "2_2") (pintype "passive"))
      (node (ref "DC1") (pin "2") (pinfunction "-VIN_2") (pintype "passive"))
      (node (ref "DC2") (pin "2") (pinfunction "-VIN_2") (pintype "passive"))
      (node (ref "DC3") (pin "2") (pinfunction "-VIN_2") (pintype "passive"))
      (node (ref "DC4") (pin "2") (pinfunction "-VIN_2") (pintype "passive"))
      (node (ref "DC5") (pin "2") (pinfunction "-VIN_2") (pintype "passive"))
      (node (ref "DC6") (pin "2") (pinfunction "-VIN_2") (pintype "passive"))
      (node (ref "LEM1") (pin "13") (pinfunction "GND_13") (pintype "bidirectional"))
      (node (ref "LEM2") (pin "13") (pinfunction "GND_13") (pintype "bidirectional"))
      (node (ref "R24") (pin "1") (pinfunction "1_1") (pintype "passive"))
      (node (ref "R27") (pin "1") (pinfunction "1_1") (pintype "passive"))
      (node (ref "R3") (pin "1") (pinfunction "1_1") (pintype "passive"))
      (node (ref "SV1") (pin "10") (pinfunction "10_10") (pintype "passive"))
      (node (ref "SV1") (pin "2") (pinfunction "2_2") (pintype "passive"))
      (node (ref "SV1") (pin "4") (pinfunction "4_4") (pintype "passive"))
      (node (ref "SV1") (pin "6") (pinfunction "6_6") (pintype "passive"))
      (node (ref "SV1") (pin "8") (pinfunction "8_8") (pintype "passive"))
      (node (ref "SV2") (pin "10") (pinfunction "10_10") (pintype "passive"))
      (node (ref "SV2") (pin "2") (pinfunction "2_2") (pintype "passive"))
      (node (ref "SV2") (pin "4") (pinfunction "4_4") (pintype "passive"))
      (node (ref "SV2") (pin "6") (pinfunction "6_6") (pintype "passive"))
      (node (ref "SV2") (pin "8") (pinfunction "8_8") (pintype "passive"))
      (node (ref "SV3") (pin "10") (pinfunction "10_10") (pintype "passive"))
      (node (ref "SV3") (pin "2") (pinfunction "2_2") (pintype "passive"))
      (node (ref "SV3") (pin "4") (pinfunction "4_4") (pintype "passive"))
      (node (ref "SV3") (pin "6") (pinfunction "6_6") (pintype "passive"))
      (node (ref "SV3") (pin "8") (pinfunction "8_8") (pintype "passive"))
      (node (ref "SV4") (pin "10") (pinfunction "10_10") (pintype "passive"))
      (node (ref "SV4") (pin "2") (pinfunction "2_2") (pintype "passive"))
      (node (ref "SV4") (pin "4") (pinfunction "4_4") (pintype "passive"))
      (node (ref "SV4") (pin "6") (pinfunction "6_6") (pintype "passive"))
      (node (ref "SV4") (pin "8") (pinfunction "8_8") (pintype "passive"))
      (node (ref "SV5") (pin "10") (pinfunction "10_10") (pintype "passive"))
      (node (ref "SV5") (pin "2") (pinfunction "2_2") (pintype "passive"))
      (node (ref "SV5") (pin "4") (pinfunction "4_4") (pintype "passive"))
      (node (ref "SV5") (pin "6") (pinfunction "6_6") (pintype "passive"))
      (node (ref "SV5") (pin "8") (pinfunction "8_8") (pintype "passive"))
      (node (ref "U1") (pin "4") (pinfunction "GND_4") (pintype "bidirectional"))
      (node (ref "U2") (pin "4") (pinfunction "GND_4") (pintype "bidirectional"))
      (node (ref "U3") (pin "4") (pinfunction "GND_4") (pintype "bidirectional"))
    )
    (net (code "25") (name "G_BOT_L1") (class "Default")
      (node (ref "R7") (pin "1") (pinfunction "1_1") (pintype "passive"))
      (node (ref "R8") (pin "1") (pinfunction "1_1") (pintype "passive"))
      (node (ref "U1") (pin "10") (pinfunction "OUTB_10") (pintype "bidirectional"))
    )
    (net (code "26") (name "G_BOT_L2") (class "Default")
      (node (ref "R16") (pin "1") (pinfunction "1_1") (pintype "passive"))
      (node (ref "R17") (pin "1") (pinfunction "1_1") (pintype "passive"))
      (node (ref "U2") (pin "10") (pinfunction "OUTB_10") (pintype "bidirectional"))
    )
    (net (code "27") (name "G_BOT_L3") (class "Default")
      (node (ref "R19") (pin "1") (pinfunction "1_1") (pintype "passive"))
      (node (ref "R20") (pin "1") (pinfunction "1_1") (pintype "passive"))
      (node (ref "U3") (pin "10") (pinfunction "OUTB_10") (pintype "bidirectional"))
    )
    (net (code "28") (name "G_TOP_L1") (class "Default")
      (node (ref "R4") (pin "1") (pinfunction "1_1") (pintype "passive"))
      (node (ref "R5") (pin "1") (pinfunction "1_1") (pintype "passive"))
      (node (ref "U1") (pin "15") (pinfunction "OUTA_15") (pintype "bidirectional"))
    )
    (net (code "29") (name "G_TOP_L2") (class "Default")
      (node (ref "R10") (pin "1") (pinfunction "1_1") (pintype "passive"))
      (node (ref "R11") (pin "1") (pinfunction "1_1") (pintype "passive"))
      (node (ref "U2") (pin "15") (pinfunction "OUTA_15") (pintype "bidirectional"))
    )
    (net (code "30") (name "G_TOP_L3") (class "Default")
      (node (ref "R13") (pin "1") (pinfunction "1_1") (pintype "passive"))
      (node (ref "R14") (pin "1") (pinfunction "1_1") (pintype "passive"))
      (node (ref "U3") (pin "15") (pinfunction "OUTA_15") (pintype "bidirectional"))
    )
    (net (code "31") (name "Net-(D1-PadA)") (class "Default")
      (node (ref "D1") (pin "A") (pinfunction "A_A") (pintype "passive"))
      (node (ref "Q2") (pin "G") (pinfunction "G_G") (pintype "passive"))
      (node (ref "R4") (pin "2") (pinfunction "2_2") (pintype "passive"))
      (node (ref "R6") (pin "1") (pinfunction "1_1") (pintype "passive"))
    )
    (net (code "32") (name "Net-(D1-PadC)") (class "Default")
      (node (ref "D1") (pin "C") (pinfunction "C_C") (pintype "passive"))
      (node (ref "R5") (pin "2") (pinfunction "2_2") (pintype "passive"))
    )
    (net (code "33") (name "Net-(D2-PadA)") (class "Default")
      (node (ref "D2") (pin "A") (pinfunction "A_A") (pintype "passive"))
      (node (ref "Q1") (pin "G") (pinfunction "G_G") (pintype "passive"))
      (node (ref "R7") (pin "2") (pinfunction "2_2") (pintype "passive"))
      (node (ref "R9") (pin "1") (pinfunction "1_1") (pintype "passive"))
    )
    (net (code "34") (name "Net-(D2-PadC)") (class "Default")
      (node (ref "D2") (pin "C") (pinfunction "C_C") (pintype "passive"))
      (node (ref "R8") (pin "2") (pinfunction "2_2") (pintype "passive"))
    )
    (net (code "35") (name "Net-(D3-PadA)") (class "Default")
      (node (ref "D3") (pin "A") (pinfunction "A_A") (pintype "passive"))
      (node (ref "Q3") (pin "G") (pinfunction "G_G") (pintype "passive"))
      (node (ref "R10") (pin "2") (pinfunction "2_2") (pintype "passive"))
      (node (ref "R12") (pin "1") (pinfunction "1_1") (pintype "passive"))
    )
    (net (code "36") (name "Net-(D3-PadC)") (class "Default")
      (node (ref "D3") (pin "C") (pinfunction "C_C") (pintype "passive"))
      (node (ref "R11") (pin "2") (pinfunction "2_2") (pintype "passive"))
    )
    (net (code "37") (name "Net-(D4-PadA)") (class "Default")
      (node (ref "D4") (pin "A") (pinfunction "A_A") (pintype "passive"))
      (node (ref "Q5") (pin "G") (pinfunction "G_G") (pintype "passive"))
      (node (ref "R13") (pin "2") (pinfunction "2_2") (pintype "passive"))
      (node (ref "R15") (pin "1") (pinfunction "1_1") (pintype "passive"))
    )
    (net (code "38") (name "Net-(D4-PadC)") (class "Default")
      (node (ref "D4") (pin "C") (pinfunction "C_C") (pintype "passive"))
      (node (ref "R14") (pin "2") (pinfunction "2_2") (pintype "passive"))
    )
    (net (code "39") (name "Net-(D5-PadA)") (class "Default")
      (node (ref "D5") (pin "A") (pinfunction "A_A") (pintype "passive"))
      (node (ref "Q4") (pin "G") (pinfunction "G_G") (pintype "passive"))
      (node (ref "R16") (pin "2") (pinfunction "2_2") (pintype "passive"))
      (node (ref "R18") (pin "1") (pinfunction "1_1") (pintype "passive"))
    )
    (net (code "40") (name "Net-(D5-PadC)") (class "Default")
      (node (ref "D5") (pin "C") (pinfunction "C_C") (pintype "passive"))
      (node (ref "R17") (pin "2") (pinfunction "2_2") (pintype "passive"))
    )
    (net (code "41") (name "Net-(D6-PadA)") (class "Default")
      (node (ref "D6") (pin "A") (pinfunction "A_A") (pintype "passive"))
      (node (ref "Q6") (pin "G") (pinfunction "G_G") (pintype "passive"))
      (node (ref "R19") (pin "2") (pinfunction "2_2") (pintype "passive"))
      (node (ref "R21") (pin "1") (pinfunction "1_1") (pintype "passive"))
    )
    (net (code "42") (name "Net-(D6-PadC)") (class "Default")
      (node (ref "D6") (pin "C") (pinfunction "C_C") (pintype "passive"))
      (node (ref "R20") (pin "2") (pinfunction "2_2") (pintype "passive"))
    )
    (net (code "43") (name "Net-(K1B-SA)") (class "Default")
      (node (ref "B1") (pin "+") (pinfunction "+_+") (pintype "passive"))
      (node (ref "K1") (pin "14A") (pinfunction "SA_14A") (pintype "passive"))
      (node (ref "K1") (pin "14B") (pinfunction "SB_14B") (pintype "passive"))
      (node (ref "R28") (pin "1") (pinfunction "1_1") (pintype "passive"))
    )
    (net (code "44") (name "Net-(U1-DT)") (class "Default")
      (node (ref "C5") (pin "2") (pinfunction "2_2") (pintype "passive"))
      (node (ref "R3") (pin "2") (pinfunction "2_2") (pintype "passive"))
      (node (ref "U1") (pin "6") (pinfunction "DT_6") (pintype "input"))
    )
    (net (code "45") (name "Net-(U1-INA)") (class "Default")
      (node (ref "C3") (pin "2") (pinfunction "2_2") (pintype "passive"))
      (node (ref "R1") (pin "2") (pinfunction "2_2") (pintype "passive"))
      (node (ref "U1") (pin "1") (pinfunction "INA_1") (pintype "bidirectional"))
    )
    (net (code "46") (name "Net-(U1-INB)") (class "Default")
      (node (ref "C2") (pin "2") (pinfunction "2_2") (pintype "passive"))
      (node (ref "R2") (pin "2") (pinfunction "2_2") (pintype "passive"))
      (node (ref "U1") (pin "2") (pinfunction "INB_2") (pintype "bidirectional"))
    )
    (net (code "47") (name "Net-(U1-VDDA)") (class "Default")
      (node (ref "C12") (pin "1") (pinfunction "1_1") (pintype "passive"))
      (node (ref "C13") (pin "1") (pinfunction "1_1") (pintype "passive"))
      (node (ref "U1") (pin "16") (pinfunction "VDDA_16") (pintype "bidirectional"))
    )
    (net (code "48") (name "Net-(U1-VSSA)") (class "Default")
      (node (ref "C14") (pin "2") (pinfunction "2_2") (pintype "passive"))
      (node (ref "C15") (pin "2") (pinfunction "2_2") (pintype "passive"))
      (node (ref "U1") (pin "14") (pinfunction "VSSA_14") (pintype "bidirectional"))
    )
    (net (code "49") (name "Net-(U2-DT)") (class "Default")
      (node (ref "C30") (pin "2") (pinfunction "2_2") (pintype "passive"))
      (node (ref "R24") (pin "2") (pinfunction "2_2") (pintype "passive"))
      (node (ref "U2") (pin "6") (pinfunction "DT_6") (pintype "input"))
    )
    (net (code "50") (name "Net-(U2-INA)") (class "Default")
      (node (ref "C28") (pin "2") (pinfunction "2_2") (pintype "passive"))
      (node (ref "R22") (pin "2") (pinfunction "2_2") (pintype "passive"))
      (node (ref "U2") (pin "1") (pinfunction "INA_1") (pintype "bidirectional"))
    )
    (net (code "51") (name "Net-(U2-INB)") (class "Default")
      (node (ref "C27") (pin "2") (pinfunction "2_2") (pintype "passive"))
      (node (ref "R23") (pin "2") (pinfunction "2_2") (pintype "passive"))
      (node (ref "U2") (pin "2") (pinfunction "INB_2") (pintype "bidirectional"))
    )
    (net (code "52") (name "Net-(U2-VDDA)") (class "Default")
      (node (ref "C37") (pin "1") (pinfunction "1_1") (pintype "passive"))
      (node (ref "C38") (pin "1") (pinfunction "1_1") (pintype "passive"))
      (node (ref "U2") (pin "16") (pinfunction "VDDA_16") (pintype "bidirectional"))
    )
    (net (code "53") (name "Net-(U2-VSSA)") (class "Default")
      (node (ref "C39") (pin "2") (pinfunction "2_2") (pintype "passive"))
      (node (ref "C40") (pin "2") (pinfunction "2_2") (pintype "passive"))
      (node (ref "U2") (pin "14") (pinfunction "VSSA_14") (pintype "bidirectional"))
    )
    (net (code "54") (name "Net-(U3-DT)") (class "Default")
      (node (ref "C55") (pin "2") (pinfunction "2_2") (pintype "passive"))
      (node (ref "R27") (pin "2") (pinfunction "2_2") (pintype "passive"))
      (node (ref "U3") (pin "6") (pinfunction "DT_6") (pintype "input"))
    )
    (net (code "55") (name "Net-(U3-INA)") (class "Default")
      (node (ref "C53") (pin "2") (pinfunction "2_2") (pintype "passive"))
      (node (ref "R25") (pin "2") (pinfunction "2_2") (pintype "passive"))
      (node (ref "U3") (pin "1") (pinfunction "INA_1") (pintype "bidirectional"))
    )
    (net (code "56") (name "Net-(U3-INB)") (class "Default")
      (node (ref "C52") (pin "2") (pinfunction "2_2") (pintype "passive"))
      (node (ref "R26") (pin "2") (pinfunction "2_2") (pintype "passive"))
      (node (ref "U3") (pin "2") (pinfunction "INB_2") (pintype "bidirectional"))
    )
    (net (code "57") (name "Net-(U3-VDDA)") (class "Default")
      (node (ref "C62") (pin "1") (pinfunction "1_1") (pintype "passive"))
      (node (ref "C63") (pin "1") (pinfunction "1_1") (pintype "passive"))
      (node (ref "U3") (pin "16") (pinfunction "VDDA_16") (pintype "bidirectional"))
    )
    (net (code "58") (name "Net-(U3-VSSA)") (class "Default")
      (node (ref "C64") (pin "2") (pinfunction "2_2") (pintype "passive"))
      (node (ref "C65") (pin "2") (pinfunction "2_2") (pintype "passive"))
      (node (ref "U3") (pin "14") (pinfunction "VSSA_14") (pintype "bidirectional"))
    )
    (net (code "59") (name "OUT_L1") (class "Default")
      (node (ref "C10") (pin "1") (pinfunction "1_1") (pintype "passive"))
      (node (ref "C11") (pin "2") (pinfunction "2_2") (pintype "passive"))
      (node (ref "C12") (pin "2") (pinfunction "2_2") (pintype "passive"))
      (node (ref "C13") (pin "2") (pinfunction "2_2") (pintype "passive"))
      (node (ref "C14") (pin "1") (pinfunction "1_1") (pintype "passive"))
      (node (ref "C15") (pin "1") (pinfunction "1_1") (pintype "passive"))
      (node (ref "C8") (pin "2") (pinfunction "2_2") (pintype "passive"))
      (node (ref "C9") (pin "1") (pinfunction "1_1") (pintype "passive"))
      (node (ref "DC1") (pin "5") (pinfunction "COM_5") (pintype "passive"))
      (node (ref "LEM1") (pin "2") (pinfunction "2_2") (pintype "bidirectional"))
      (node (ref "LEM1") (pin "3") (pinfunction "3_3") (pintype "bidirectional"))
      (node (ref "LEM1") (pin "4") (pinfunction "4_4") (pintype "bidirectional"))
      (node (ref "LEM1") (pin "5") (pinfunction "5_5") (pintype "bidirectional"))
      (node (ref "Q1") (pin "D") (pinfunction "D_D") (pintype "passive"))
      (node (ref "Q2") (pin "S") (pinfunction "S_S") (pintype "passive"))
      (node (ref "R6") (pin "2") (pinfunction "2_2") (pintype "passive"))
    )
    (net (code "60") (name "OUT_L1_LEM") (class "Default")
      (node (ref "LEM1") (pin "6") (pinfunction "6_6") (pintype "bidirectional"))
      (node (ref "LEM1") (pin "7") (pinfunction "7_7") (pintype "bidirectional"))
      (node (ref "LEM1") (pin "8") (pinfunction "8_8") (pintype "bidirectional"))
      (node (ref "LEM1") (pin "9") (pinfunction "9_9") (pintype "bidirectional"))
      (node (ref "X2") (pin "3") (pinfunction "1_3") (pintype "passive"))
    )
    (net (code "61") (name "OUT_L2") (class "Default")
      (node (ref "C33") (pin "2") (pinfunction "2_2") (pintype "passive"))
      (node (ref "C34") (pin "1") (pinfunction "1_1") (pintype "passive"))
      (node (ref "C35") (pin "1") (pinfunction "1_1") (pintype "passive"))
      (node (ref "C36") (pin "2") (pinfunction "2_2") (pintype "passive"))
      (node (ref "C37") (pin "2") (pinfunction "2_2") (pintype "passive"))
      (node (ref "C38") (pin "2") (pinfunction "2_2") (pintype "passive"))
      (node (ref "C39") (pin "1") (pinfunction "1_1") (pintype "passive"))
      (node (ref "C40") (pin "1") (pinfunction "1_1") (pintype "passive"))
      (node (ref "DC3") (pin "5") (pinfunction "COM_5") (pintype "passive"))
      (node (ref "LEM2") (pin "2") (pinfunction "2_2") (pintype "bidirectional"))
      (node (ref "LEM2") (pin "3") (pinfunction "3_3") (pintype "bidirectional"))
      (node (ref "LEM2") (pin "4") (pinfunction "4_4") (pintype "bidirectional"))
      (node (ref "LEM2") (pin "5") (pinfunction "5_5") (pintype "bidirectional"))
      (node (ref "Q3") (pin "S") (pinfunction "S_S") (pintype "passive"))
      (node (ref "Q4") (pin "D") (pinfunction "D_D") (pintype "passive"))
      (node (ref "R12") (pin "2") (pinfunction "2_2") (pintype "passive"))
    )
    (net (code "62") (name "OUT_L2_LEM") (class "Default")
      (node (ref "LEM2") (pin "6") (pinfunction "6_6") (pintype "bidirectional"))
      (node (ref "LEM2") (pin "7") (pinfunction "7_7") (pintype "bidirectional"))
      (node (ref "LEM2") (pin "8") (pinfunction "8_8") (pintype "bidirectional"))
      (node (ref "LEM2") (pin "9") (pinfunction "9_9") (pintype "bidirectional"))
      (node (ref "X2") (pin "2") (pinfunction "1_2") (pintype "passive"))
    )
    (net (code "63") (name "OUT_L3") (class "Default")
      (node (ref "C58") (pin "2") (pinfunction "2_2") (pintype "passive"))
      (node (ref "C59") (pin "1") (pinfunction "1_1") (pintype "passive"))
      (node (ref "C60") (pin "1") (pinfunction "1_1") (pintype "passive"))
      (node (ref "C61") (pin "2") (pinfunction "2_2") (pintype "passive"))
      (node (ref "C62") (pin "2") (pinfunction "2_2") (pintype "passive"))
      (node (ref "C63") (pin "2") (pinfunction "2_2") (pintype "passive"))
      (node (ref "C64") (pin "1") (pinfunction "1_1") (pintype "passive"))
      (node (ref "C65") (pin "1") (pinfunction "1_1") (pintype "passive"))
      (node (ref "DC5") (pin "5") (pinfunction "COM_5") (pintype "passive"))
      (node (ref "Q5") (pin "S") (pinfunction "S_S") (pintype "passive"))
      (node (ref "Q6") (pin "D") (pinfunction "D_D") (pintype "passive"))
      (node (ref "R15") (pin "2") (pinfunction "2_2") (pintype "passive"))
      (node (ref "X2") (pin "1") (pinfunction "1_1") (pintype "passive"))
    )
    (net (code "64") (name "PRE_A1") (class "Default")
      (node (ref "D7") (pin "C") (pinfunction "C_C") (pintype "passive"))
      (node (ref "K1") (pin "A1") (pinfunction "1_A1") (pintype "passive"))
      (node (ref "SV2") (pin "3") (pinfunction "3_3") (pintype "passive"))
    )
    (net (code "65") (name "PRE_A2") (class "Default")
      (node (ref "D7") (pin "A") (pinfunction "A_A") (pintype "passive"))
      (node (ref "K1") (pin "A2") (pinfunction "2_A2") (pintype "passive"))
      (node (ref "SV2") (pin "1") (pinfunction "1_1") (pintype "passive"))
    )
    (net (code "66") (name "PWM_BOT_L1") (class "Default")
      (node (ref "R2") (pin "1") (pinfunction "1_1") (pintype "passive"))
      (node (ref "SV3") (pin "3") (pinfunction "3_3") (pintype "passive"))
    )
    (net (code "67") (name "PWM_BOT_L2") (class "Default")
      (node (ref "R23") (pin "1") (pinfunction "1_1") (pintype "passive"))
      (node (ref "SV4") (pin "3") (pinfunction "3_3") (pintype "passive"))
    )
    (net (code "68") (name "PWM_BOT_L3") (class "Default")
      (node (ref "R26") (pin "1") (pinfunction "1_1") (pintype "passive"))
      (node (ref "SV5") (pin "3") (pinfunction "3_3") (pintype "passive"))
    )
    (net (code "69") (name "PWM_PIN_EN_L1") (class "Default")
      (node (ref "C4") (pin "2") (pinfunction "2_2") (pintype "passive"))
      (node (ref "SV3") (pin "5") (pinfunction "5_5") (pintype "passive"))
      (node (ref "U1") (pin "5") (pinfunction "EN_5") (pintype "input"))
    )
    (net (code "70") (name "PWM_PIN_EN_L2") (class "Default")
      (node (ref "C29") (pin "2") (pinfunction "2_2") (pintype "passive"))
      (node (ref "SV4") (pin "5") (pinfunction "5_5") (pintype "passive"))
      (node (ref "U2") (pin "5") (pinfunction "EN_5") (pintype "input"))
    )
    (net (code "71") (name "PWM_PIN_EN_L3") (class "Default")
      (node (ref "C54") (pin "2") (pinfunction "2_2") (pintype "passive"))
      (node (ref "SV5") (pin "5") (pinfunction "5_5") (pintype "passive"))
      (node (ref "U3") (pin "5") (pinfunction "EN_5") (pintype "input"))
    )
    (net (code "72") (name "PWM_TOP_L1") (class "Default")
      (node (ref "R1") (pin "1") (pinfunction "1_1") (pintype "passive"))
      (node (ref "SV3") (pin "1") (pinfunction "1_1") (pintype "passive"))
    )
    (net (code "73") (name "PWM_TOP_L2") (class "Default")
      (node (ref "R22") (pin "1") (pinfunction "1_1") (pintype "passive"))
      (node (ref "SV4") (pin "1") (pinfunction "1_1") (pintype "passive"))
    )
    (net (code "74") (name "PWM_TOP_L3") (class "Default")
      (node (ref "R25") (pin "1") (pinfunction "1_1") (pintype "passive"))
      (node (ref "SV5") (pin "1") (pinfunction "1_1") (pintype "passive"))
    )
    (net (code "75") (name "UOUT_LEM_L1") (class "Default")
      (node (ref "LEM1") (pin "12") (pinfunction "VOUT_12") (pintype "bidirectional"))
      (node (ref "SV1") (pin "7") (pinfunction "7_7") (pintype "passive"))
    )
    (net (code "76") (name "UOUT_LEM_L2") (class "Default")
      (node (ref "LEM2") (pin "12") (pinfunction "VOUT_12") (pintype "bidirectional"))
      (node (ref "SV1") (pin "1") (pinfunction "1_1") (pintype "passive"))
    )
    (net (code "77") (name "UREF_LEM_L1") (class "Default")
      (node (ref "LEM1") (pin "11") (pinfunction "VREF_11") (pintype "bidirectional"))
      (node (ref "SV1") (pin "9") (pinfunction "9_9") (pintype "passive"))
    )
    (net (code "78") (name "UREF_LEM_L2") (class "Default")
      (node (ref "LEM2") (pin "11") (pinfunction "VREF_11") (pintype "bidirectional"))
      (node (ref "SV1") (pin "3") (pinfunction "3_3") (pintype "passive"))
    )
    (net (code "79") (name "unconnected-(SV1-Pad5)") (class "Default")
      (node (ref "SV1") (pin "5") (pinfunction "5_5") (pintype "passive"))
    )
    (net (code "80") (name "unconnected-(SV3-Pad7)") (class "Default")
      (node (ref "SV3") (pin "7") (pinfunction "7_7") (pintype "passive"))
    )
    (net (code "81") (name "unconnected-(SV3-Pad9)") (class "Default")
      (node (ref "SV3") (pin "9") (pinfunction "9_9") (pintype "passive"))
    )
    (net (code "82") (name "unconnected-(SV4-Pad7)") (class "Default")
      (node (ref "SV4") (pin "7") (pinfunction "7_7") (pintype "passive"))
    )
    (net (code "83") (name "unconnected-(SV4-Pad9)") (class "Default")
      (node (ref "SV4") (pin "9") (pinfunction "9_9") (pintype "passive"))
    )
    (net (code "84") (name "unconnected-(SV5-Pad7)") (class "Default")
      (node (ref "SV5") (pin "7") (pinfunction "7_7") (pintype "passive"))
    )
    (net (code "85") (name "unconnected-(SV5-Pad9)") (class "Default")
      (node (ref "SV5") (pin "9") (pinfunction "9_9") (pintype "passive"))
    )
    (net (code "86") (name "unconnected-(U1-NC-Pad7)") (class "Default")
      (node (ref "U1") (pin "7") (pinfunction "NC_7") (pintype "bidirectional"))
    )
    (net (code "87") (name "unconnected-(U2-NC-Pad7)") (class "Default")
      (node (ref "U2") (pin "7") (pinfunction "NC_7") (pintype "bidirectional"))
    )
    (net (code "88") (name "unconnected-(U3-NC-Pad7)") (class "Default")
      (node (ref "U3") (pin "7") (pinfunction "NC_7") (pintype "bidirectional"))
    )
  )
)
